# LinuxBoard_v1_0.net
KiCad netlist of a schematic drawn in EAGLE
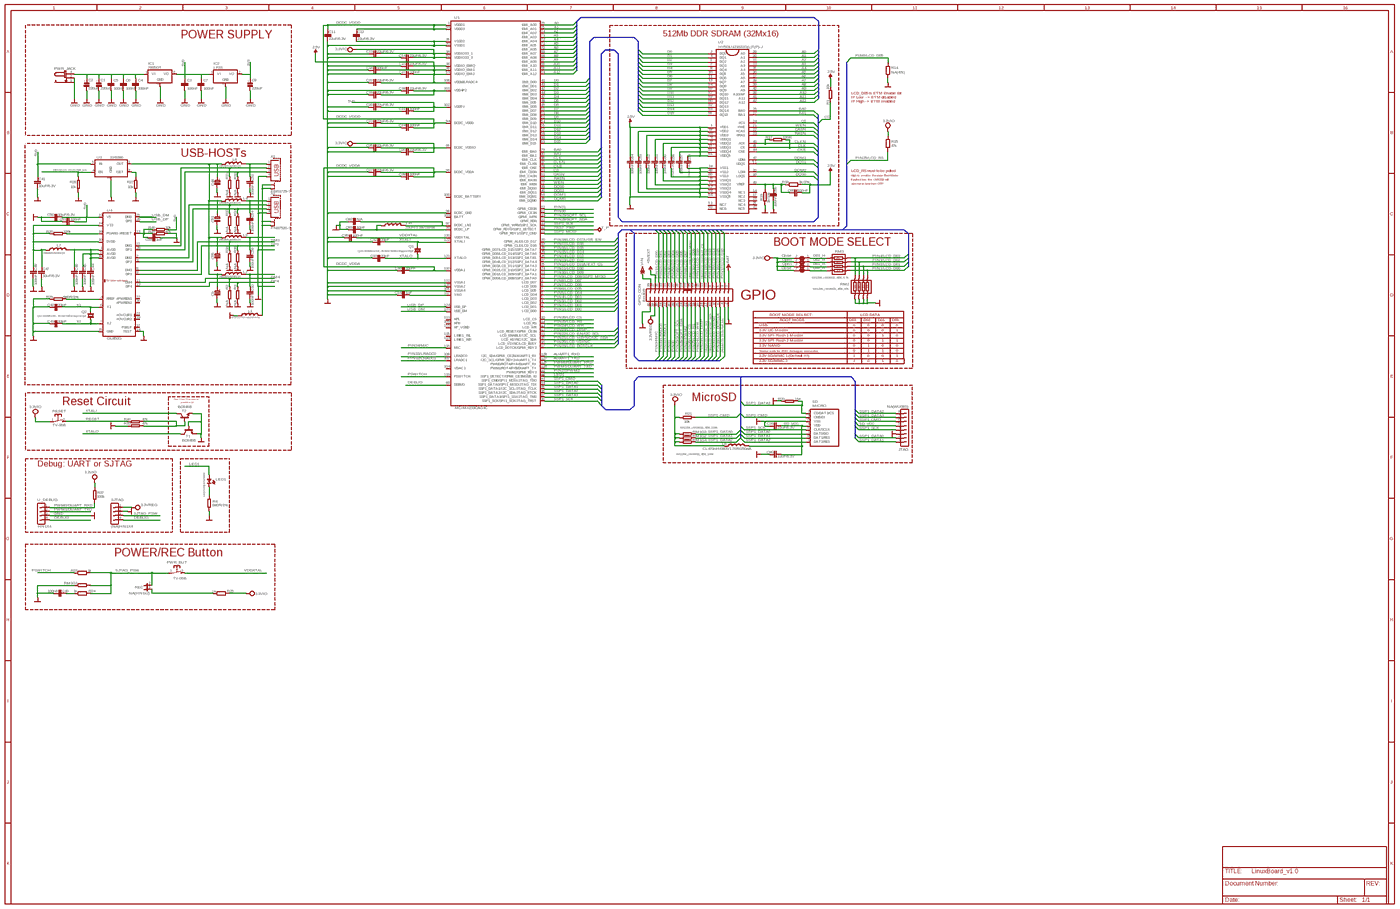
[diagram p0: schematic, sheet 1, overview]
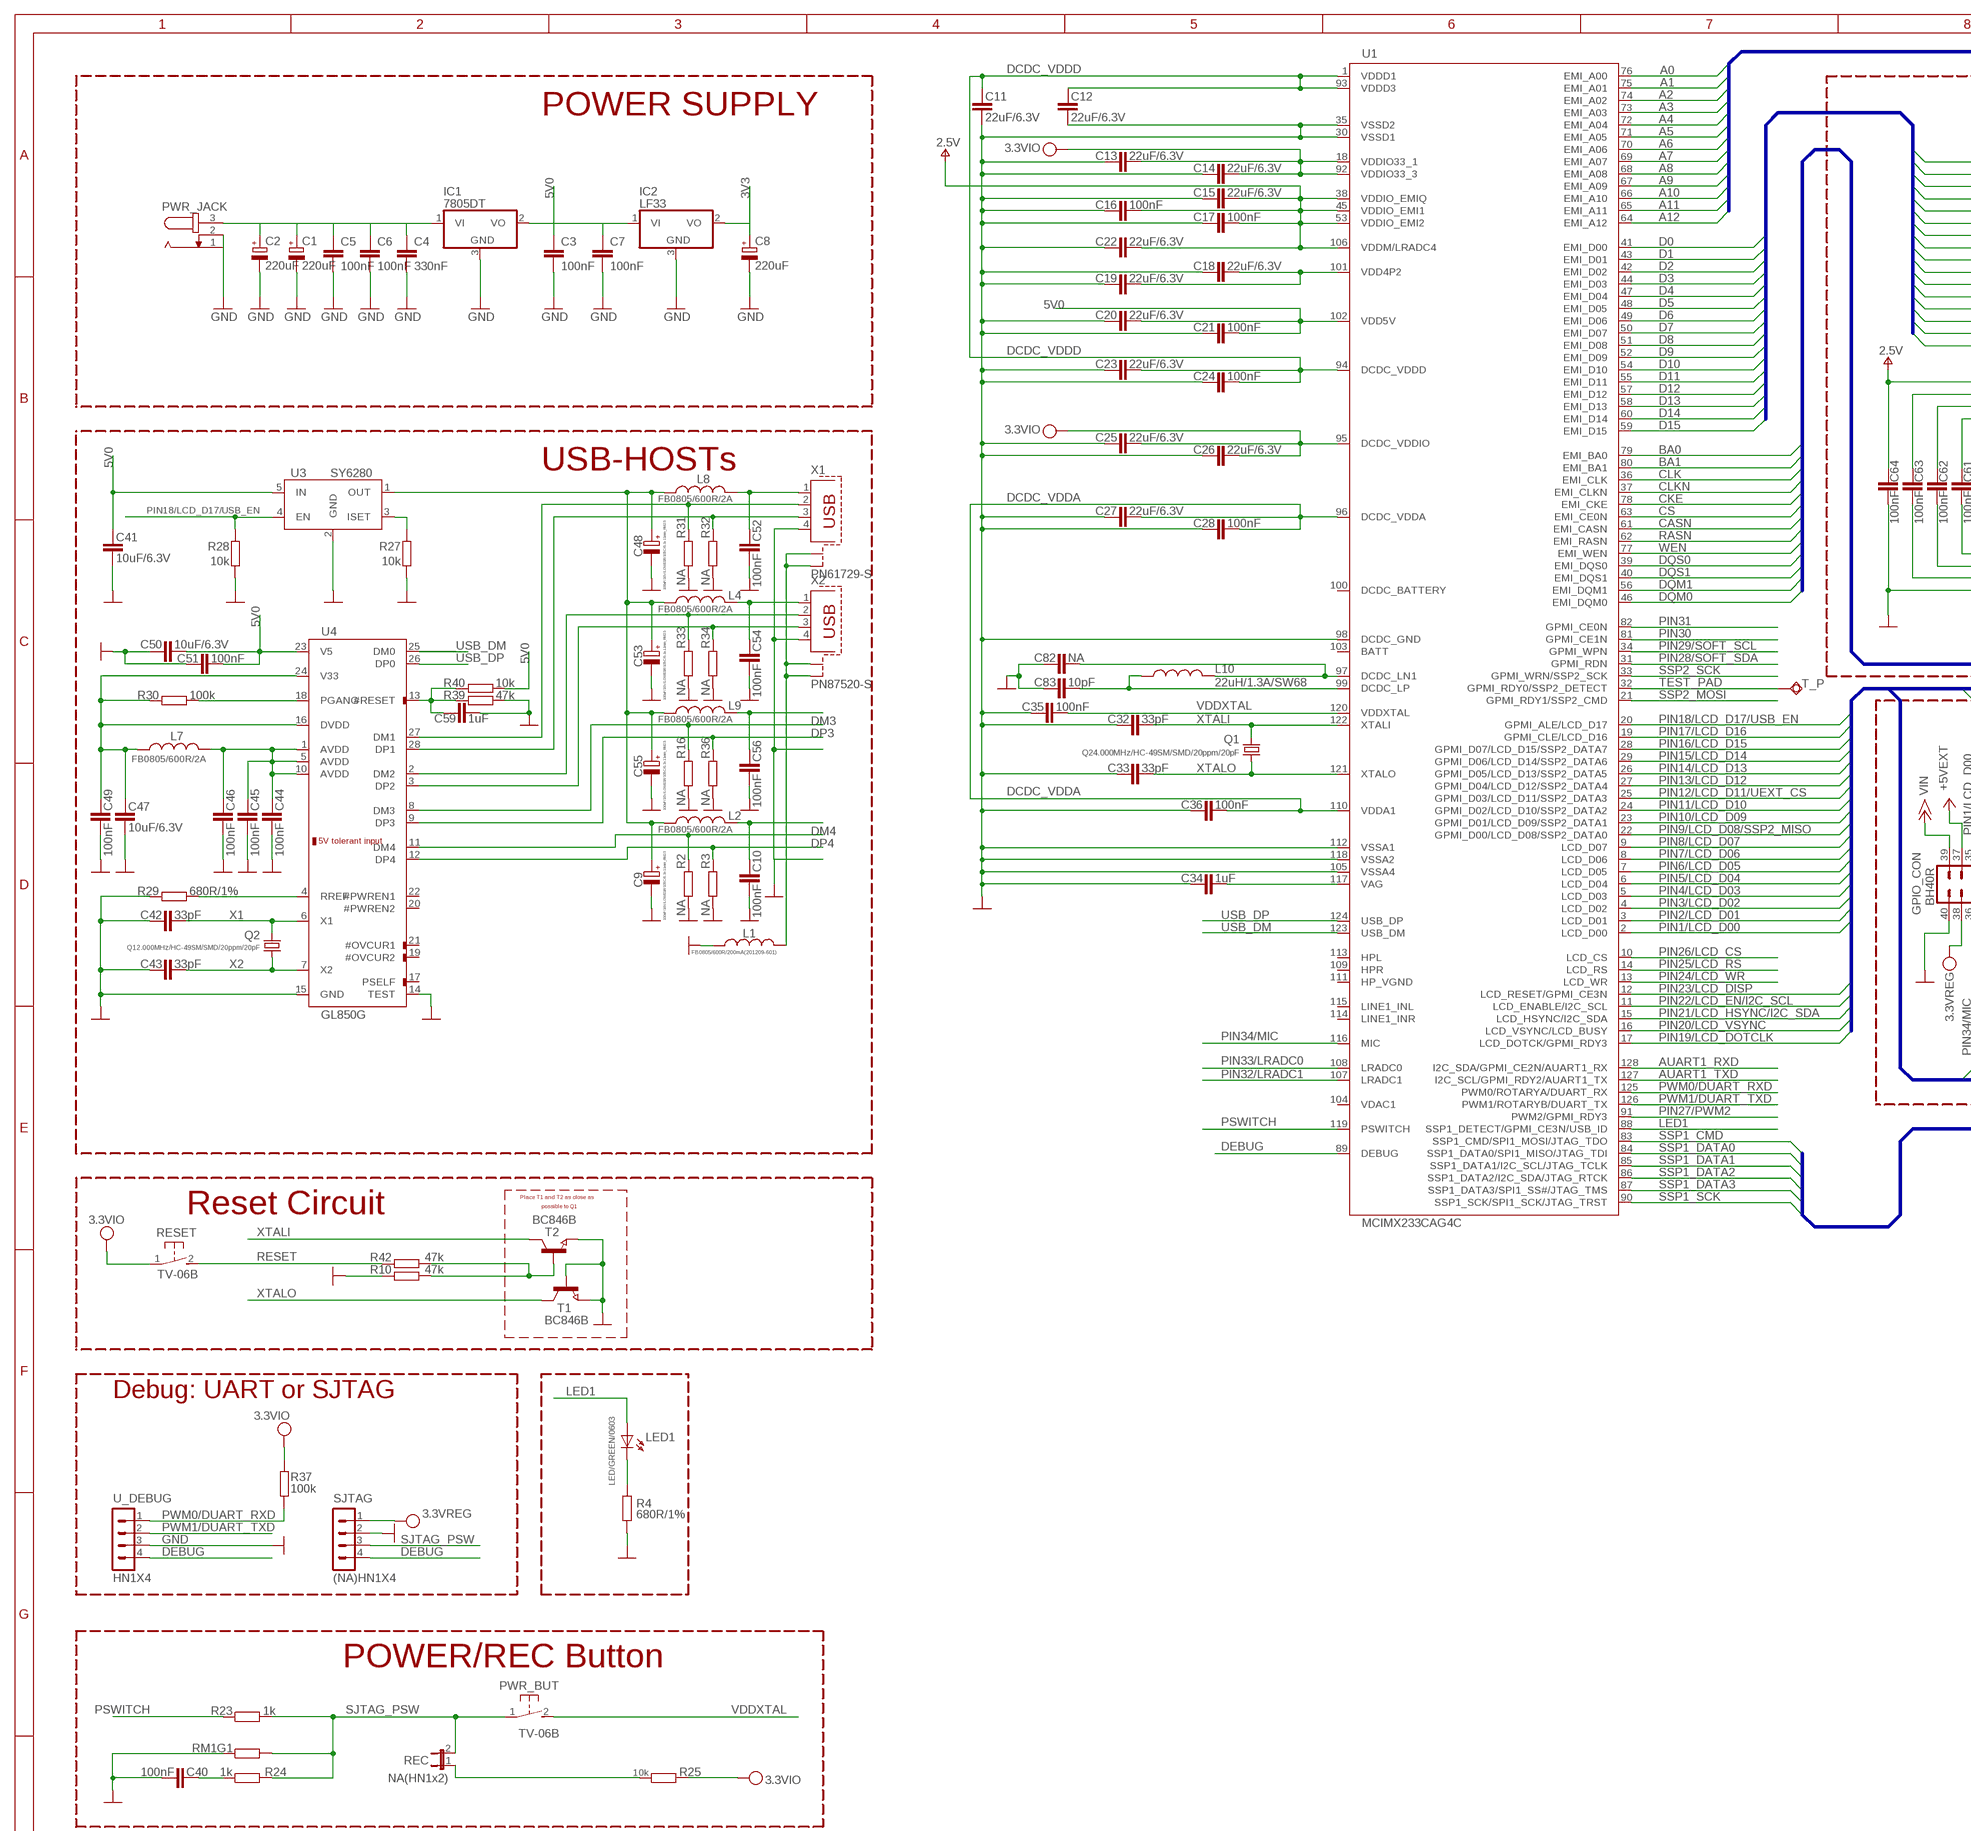
[diagram p1: schematic, sheet 1, part 1 of 4]
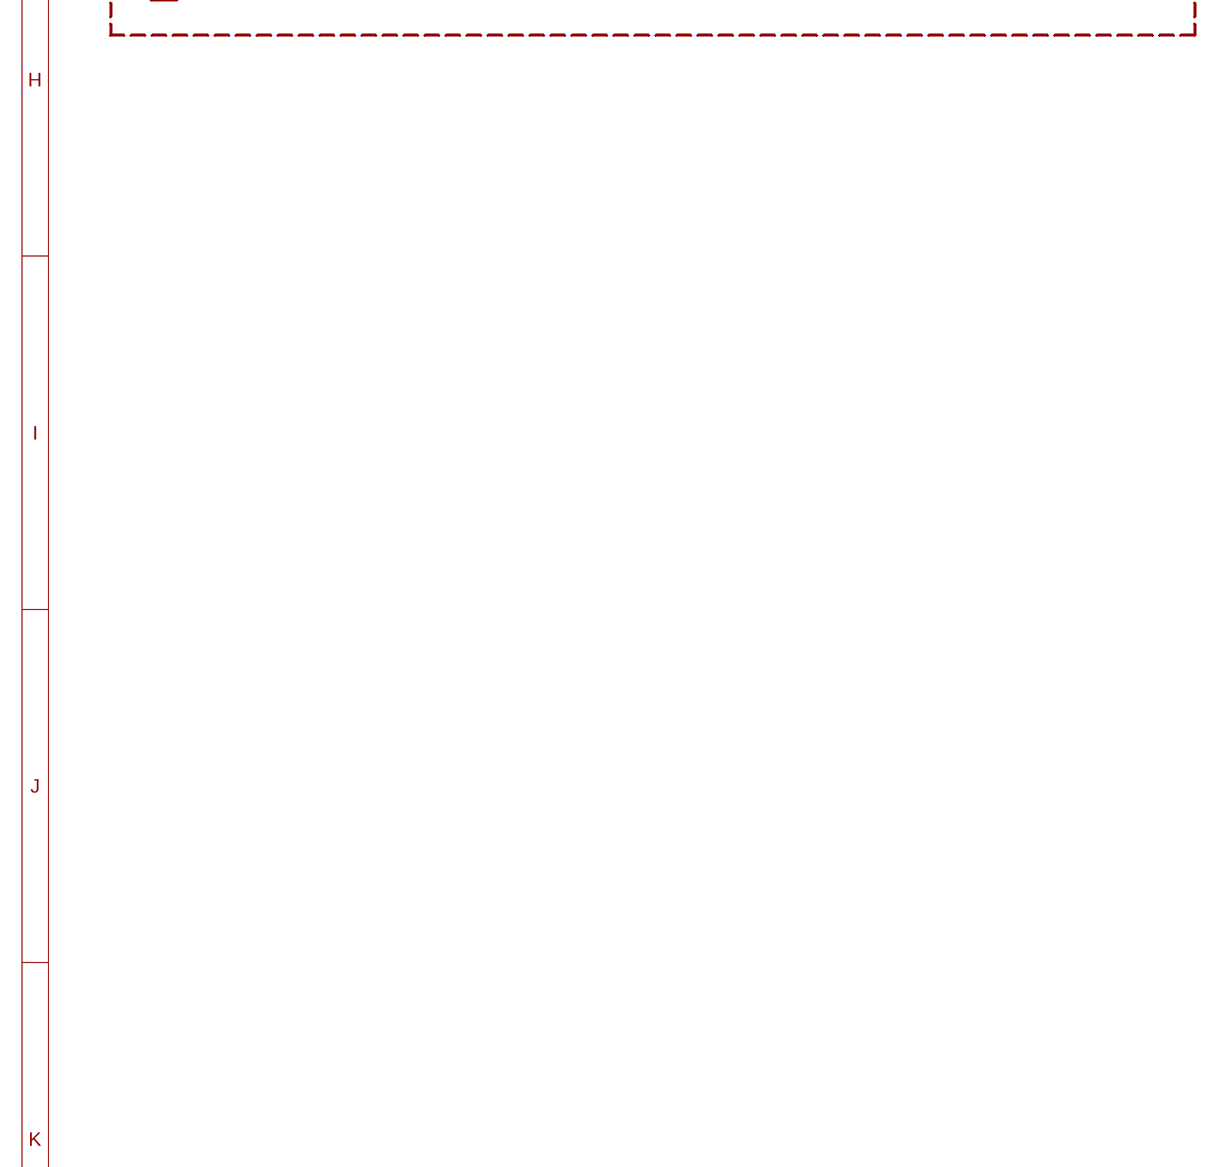
[diagram p2: schematic, sheet 1, part 2 of 4]
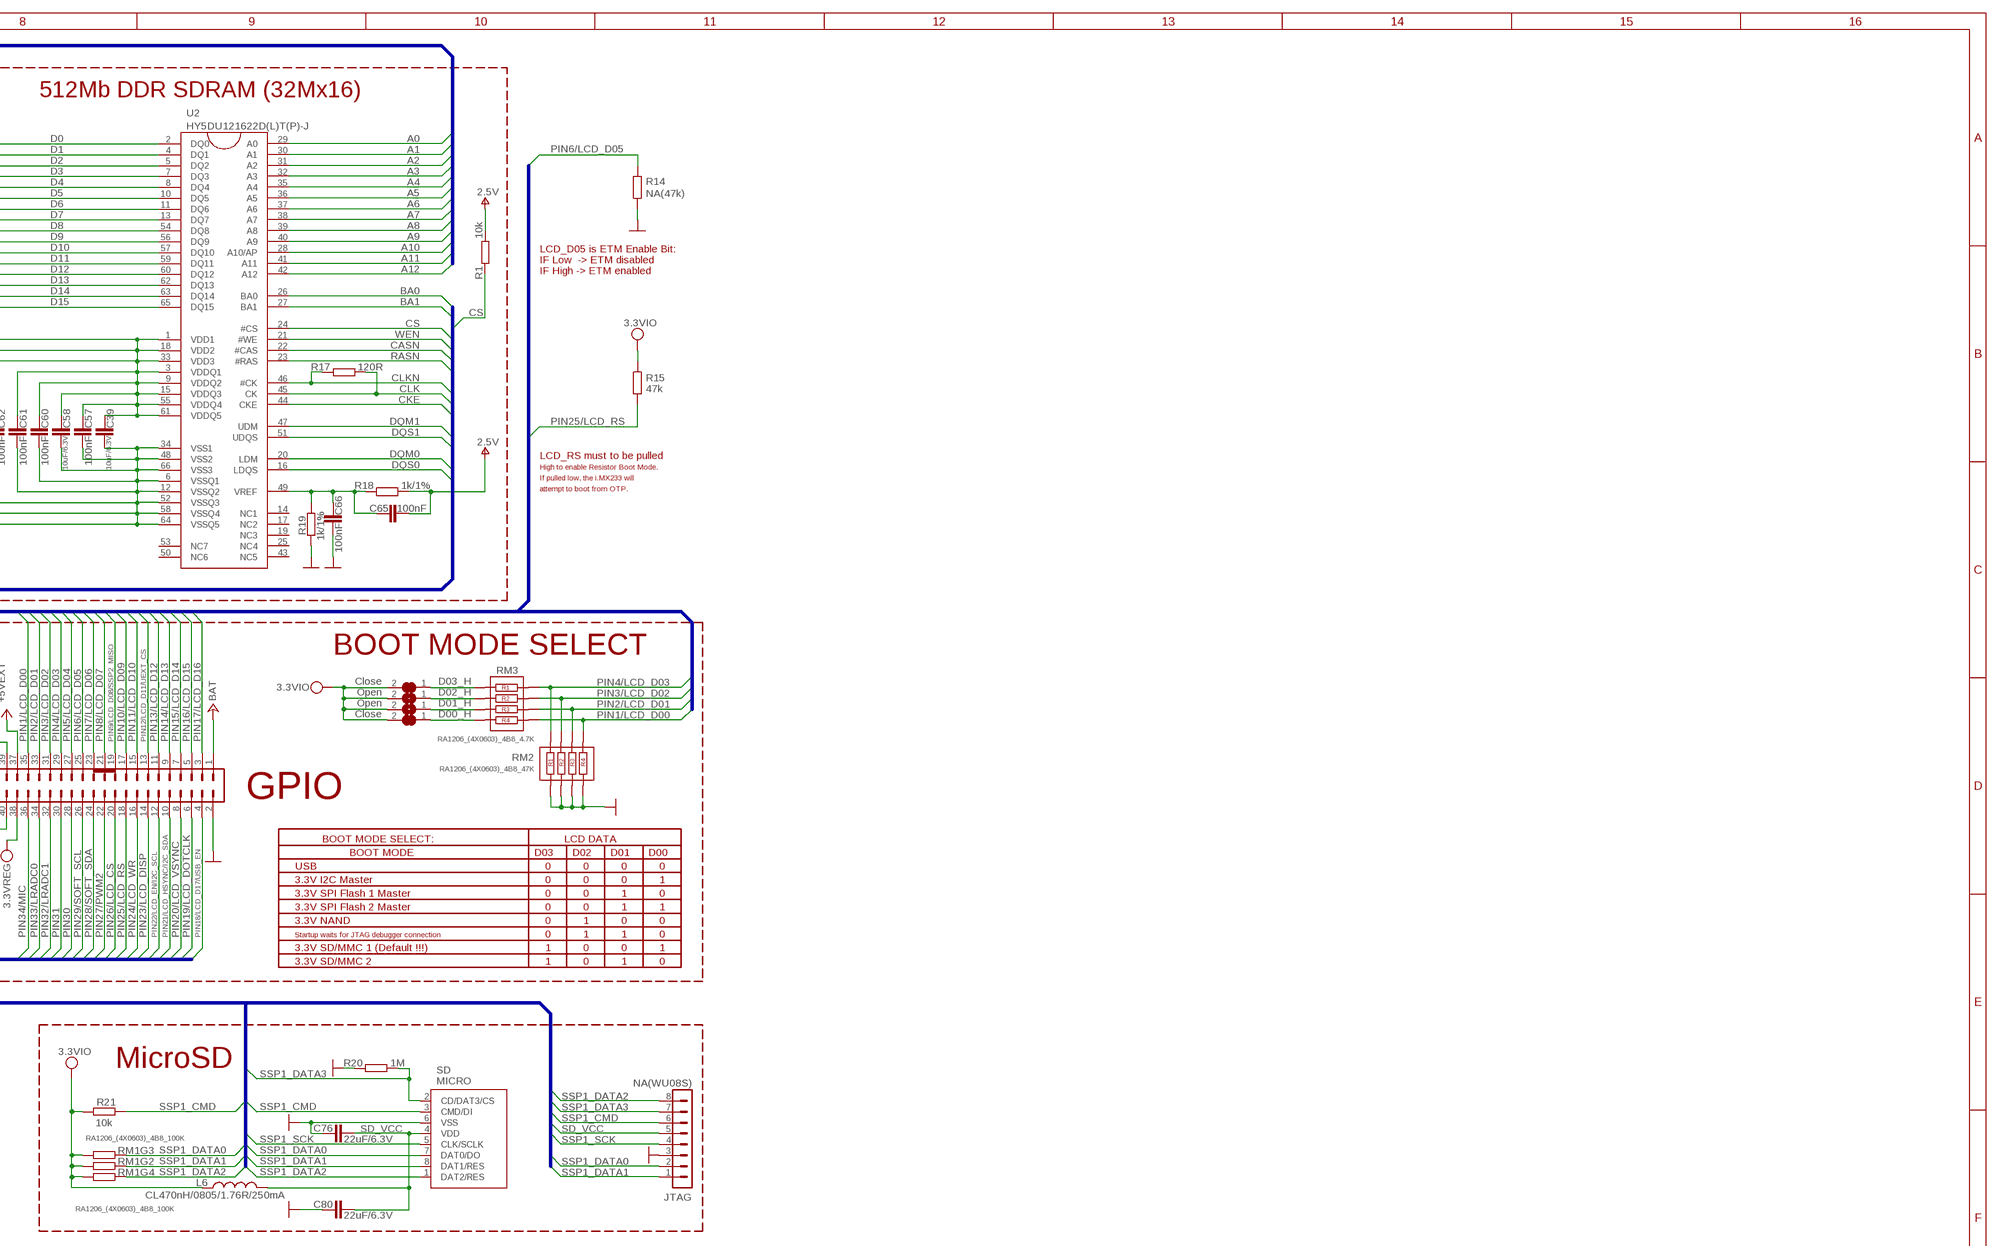
[diagram p3: schematic, sheet 1, part 3 of 4]
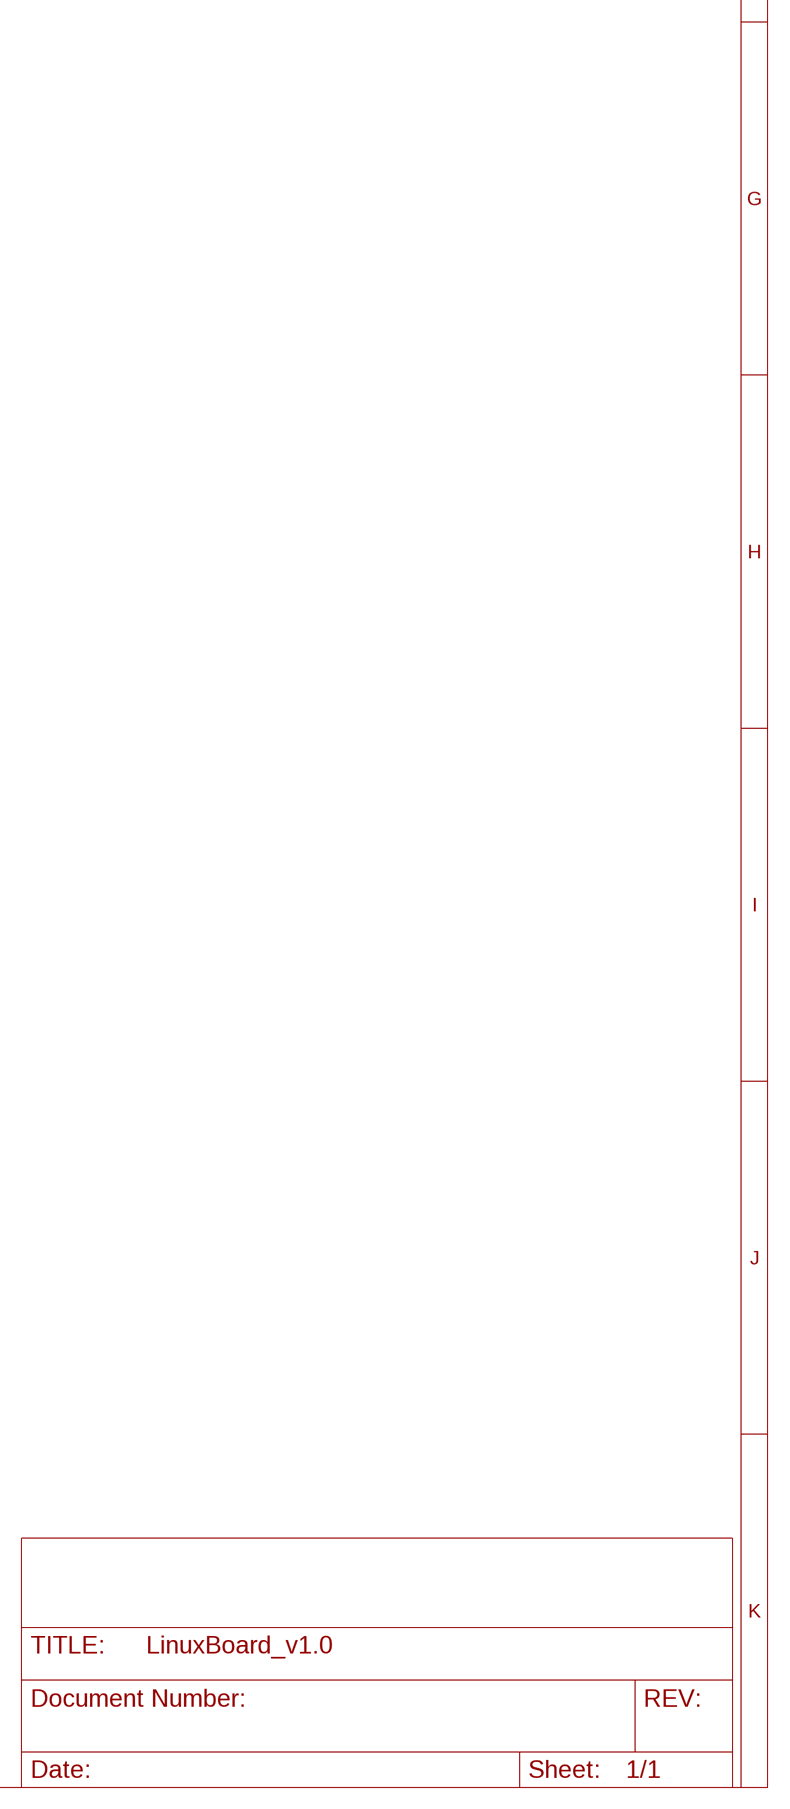
[diagram p4: schematic, sheet 1, part 4 of 4]

(export (version "E")
  (design (tool "Eeschema 10.0.6"))
  (components
    (comp (ref "C1")
      (value "220uF")
      (footprint "eagle-import:E2-5")
      (libsource (lib "eagle-import") (part "CPOL-EUE2-5"))
    )
    (comp (ref "C2")
      (value "220uF")
      (footprint "eagle-import:E2-5")
      (libsource (lib "eagle-import") (part "CPOL-EUE2-5"))
    )
    (comp (ref "C3")
      (value "100nF")
      (footprint "eagle-import:C0805")
      (libsource (lib "eagle-import") (part "C-EUC0805"))
    )
    (comp (ref "C4")
      (value "330nF")
      (footprint "eagle-import:C0805")
      (libsource (lib "eagle-import") (part "C-EUC0805"))
    )
    (comp (ref "C5")
      (value "100nF")
      (footprint "eagle-import:C0805")
      (libsource (lib "eagle-import") (part "C-EUC0805"))
    )
    (comp (ref "C6")
      (value "100nF")
      (footprint "eagle-import:C0805")
      (libsource (lib "eagle-import") (part "C-EUC0805"))
    )
    (comp (ref "C7")
      (value "100nF")
      (footprint "eagle-import:C0805")
      (libsource (lib "eagle-import") (part "C-EUC0805"))
    )
    (comp (ref "C8")
      (value "220uF")
      (footprint "eagle-import:E2-5")
      (libsource (lib "eagle-import") (part "CPOL-EUE2-5"))
    )
    (comp (ref "C9")
      (value "100uF/16V/LOWESR/105C/6.3x11mm_RM2.5")
      (footprint "eagle-import:E2,5-6,3")
      (libsource (lib "eagle-import") (part "CPOL-EUE2.5-6.3"))
    )
    (comp (ref "C10")
      (value "100nF")
      (footprint "eagle-import:C0603_DWS")
      (libsource (lib "eagle-import") (part "C-EUC0603_DWS"))
    )
    (comp (ref "C11")
      (value "22uF/6.3V")
      (footprint "eagle-import:C0805_5MIL_DWS")
      (libsource (lib "eagle-import") (part "C-EUC0805_5MIL_DWS"))
    )
    (comp (ref "C12")
      (value "22uF/6.3V")
      (footprint "eagle-import:C0805_5MIL_DWS")
      (libsource (lib "eagle-import") (part "C-EUC0805_5MIL_DWS"))
    )
    (comp (ref "C13")
      (value "22uF/6.3V")
      (footprint "eagle-import:C0805_5MIL_DWS")
      (libsource (lib "eagle-import") (part "C-EUC0805_5MIL_DWS"))
    )
    (comp (ref "C14")
      (value "22uF/6.3V")
      (footprint "eagle-import:C0805_5MIL_DWS")
      (libsource (lib "eagle-import") (part "C-EUC0805_5MIL_DWS"))
    )
    (comp (ref "C15")
      (value "22uF/6.3V")
      (footprint "eagle-import:C0805_5MIL_DWS")
      (libsource (lib "eagle-import") (part "C-EUC0805_5MIL_DWS"))
    )
    (comp (ref "C16")
      (value "100nF")
      (footprint "eagle-import:C0603_DWS")
      (libsource (lib "eagle-import") (part "C-EUC0603_DWS"))
    )
    (comp (ref "C17")
      (value "100nF")
      (footprint "eagle-import:C0603_DWS")
      (libsource (lib "eagle-import") (part "C-EUC0603_DWS"))
    )
    (comp (ref "C18")
      (value "22uF/6.3V")
      (footprint "eagle-import:C0805_5MIL_DWS")
      (libsource (lib "eagle-import") (part "C-EUC0805_5MIL_DWS"))
    )
    (comp (ref "C19")
      (value "22uF/6.3V")
      (footprint "eagle-import:C0805_5MIL_DWS")
      (libsource (lib "eagle-import") (part "C-EUC0805_5MIL_DWS"))
    )
    (comp (ref "C20")
      (value "22uF/6.3V")
      (footprint "eagle-import:C0805_5MIL_DWS")
      (libsource (lib "eagle-import") (part "C-EUC0805_5MIL_DWS"))
    )
    (comp (ref "C21")
      (value "100nF")
      (footprint "eagle-import:C0603_DWS")
      (libsource (lib "eagle-import") (part "C-EUC0603_DWS"))
    )
    (comp (ref "C22")
      (value "22uF/6.3V")
      (footprint "eagle-import:C0805_5MIL_DWS")
      (libsource (lib "eagle-import") (part "C-EUC0805_5MIL_DWS"))
    )
    (comp (ref "C23")
      (value "22uF/6.3V")
      (footprint "eagle-import:C0805_5MIL_DWS")
      (libsource (lib "eagle-import") (part "C-EUC0805_5MIL_DWS"))
    )
    (comp (ref "C24")
      (value "100nF")
      (footprint "eagle-import:C0603_DWS")
      (libsource (lib "eagle-import") (part "C-EUC0603_DWS"))
    )
    (comp (ref "C25")
      (value "22uF/6.3V")
      (footprint "eagle-import:C0805_5MIL_DWS")
      (libsource (lib "eagle-import") (part "C-EUC0805_5MIL_DWS"))
    )
    (comp (ref "C26")
      (value "22uF/6.3V")
      (footprint "eagle-import:C0805_5MIL_DWS")
      (libsource (lib "eagle-import") (part "C-EUC0805_5MIL_DWS"))
    )
    (comp (ref "C27")
      (value "22uF/6.3V")
      (footprint "eagle-import:C0805_5MIL_DWS")
      (libsource (lib "eagle-import") (part "C-EUC0805_5MIL_DWS"))
    )
    (comp (ref "C28")
      (value "100nF")
      (footprint "eagle-import:C0603_DWS")
      (libsource (lib "eagle-import") (part "C-EUC0603_DWS"))
    )
    (comp (ref "C32")
      (value "33pF")
      (footprint "eagle-import:C0603_DWS")
      (libsource (lib "eagle-import") (part "C-EUC0603_DWS"))
    )
    (comp (ref "C33")
      (value "33pF")
      (footprint "eagle-import:C0603_DWS")
      (libsource (lib "eagle-import") (part "C-EUC0603_DWS"))
    )
    (comp (ref "C34")
      (value "1uF")
      (footprint "eagle-import:C0603_DWS")
      (libsource (lib "eagle-import") (part "C-EUC0603_DWS"))
    )
    (comp (ref "C35")
      (value "100nF")
      (footprint "eagle-import:C0603_DWS")
      (libsource (lib "eagle-import") (part "C-EUC0603_DWS"))
    )
    (comp (ref "C36")
      (value "100nF")
      (footprint "eagle-import:C0603_DWS")
      (libsource (lib "eagle-import") (part "C-EUC0603_DWS"))
    )
    (comp (ref "C39")
      (value "10uF/6.3V")
      (footprint "eagle-import:C0603_DWS")
      (libsource (lib "eagle-import") (part "C-EUC0603_DWS"))
    )
    (comp (ref "C40")
      (value "100nF")
      (footprint "eagle-import:C0603_DWS")
      (libsource (lib "eagle-import") (part "C-EUC0603_DWS"))
    )
    (comp (ref "C41")
      (value "10uF/6.3V")
      (footprint "eagle-import:C0603_DWS")
      (libsource (lib "eagle-import") (part "C-EUC0603_DWS"))
    )
    (comp (ref "C42")
      (value "33pF")
      (footprint "eagle-import:C0603_DWS")
      (libsource (lib "eagle-import") (part "C-EUC0603_DWS"))
    )
    (comp (ref "C43")
      (value "33pF")
      (footprint "eagle-import:C0603_DWS")
      (libsource (lib "eagle-import") (part "C-EUC0603_DWS"))
    )
    (comp (ref "C44")
      (value "100nF")
      (footprint "eagle-import:C0603_DWS")
      (libsource (lib "eagle-import") (part "C-EUC0603_DWS"))
    )
    (comp (ref "C45")
      (value "100nF")
      (footprint "eagle-import:C0603_DWS")
      (libsource (lib "eagle-import") (part "C-EUC0603_DWS"))
    )
    (comp (ref "C46")
      (value "100nF")
      (footprint "eagle-import:C0603_DWS")
      (libsource (lib "eagle-import") (part "C-EUC0603_DWS"))
    )
    (comp (ref "C47")
      (value "10uF/6.3V")
      (footprint "eagle-import:C0603_DWS")
      (libsource (lib "eagle-import") (part "C-EUC0603_DWS"))
    )
    (comp (ref "C48")
      (value "100uF/16V/LOWESR/105C/6.3x11mm_RM2.5")
      (footprint "eagle-import:E2,5-6,3")
      (libsource (lib "eagle-import") (part "CPOL-EUE2.5-6.3"))
    )
    (comp (ref "C49")
      (value "100nF")
      (footprint "eagle-import:C0603_DWS")
      (libsource (lib "eagle-import") (part "C-EUC0603_DWS"))
    )
    (comp (ref "C50")
      (value "10uF/6.3V")
      (footprint "eagle-import:C0603_DWS")
      (libsource (lib "eagle-import") (part "C-EUC0603_DWS"))
    )
    (comp (ref "C51")
      (value "100nF")
      (footprint "eagle-import:C0603_DWS")
      (libsource (lib "eagle-import") (part "C-EUC0603_DWS"))
    )
    (comp (ref "C52")
      (value "100nF")
      (footprint "eagle-import:C0603_DWS")
      (libsource (lib "eagle-import") (part "C-EUC0603_DWS"))
    )
    (comp (ref "C53")
      (value "100uF/16V/LOWESR/105C/6.3x11mm_RM2.5")
      (footprint "eagle-import:E2,5-6,3")
      (libsource (lib "eagle-import") (part "CPOL-EUE2.5-6.3"))
    )
    (comp (ref "C54")
      (value "100nF")
      (footprint "eagle-import:C0603_DWS")
      (libsource (lib "eagle-import") (part "C-EUC0603_DWS"))
    )
    (comp (ref "C55")
      (value "100uF/16V/LOWESR/105C/6.3x11mm_RM2.5")
      (footprint "eagle-import:E2,5-6,3")
      (libsource (lib "eagle-import") (part "CPOL-EUE2.5-6.3"))
    )
    (comp (ref "C56")
      (value "100nF")
      (footprint "eagle-import:C0603_DWS")
      (libsource (lib "eagle-import") (part "C-EUC0603_DWS"))
    )
    (comp (ref "C57")
      (value "100nF")
      (footprint "eagle-import:C0603_DWS")
      (libsource (lib "eagle-import") (part "C-EUC0603_DWS"))
    )
    (comp (ref "C58")
      (value "10uF/6.3V")
      (footprint "eagle-import:C0603_DWS")
      (libsource (lib "eagle-import") (part "C-EUC0603_DWS"))
    )
    (comp (ref "C59")
      (value "1uF")
      (footprint "eagle-import:C0603_DWS")
      (libsource (lib "eagle-import") (part "C-EUC0603_DWS"))
    )
    (comp (ref "C60")
      (value "100nF")
      (footprint "eagle-import:C0603_DWS")
      (libsource (lib "eagle-import") (part "C-EUC0603_DWS"))
    )
    (comp (ref "C61")
      (value "100nF")
      (footprint "eagle-import:C0603_DWS")
      (libsource (lib "eagle-import") (part "C-EUC0603_DWS"))
    )
    (comp (ref "C62")
      (value "100nF")
      (footprint "eagle-import:C0603_DWS")
      (libsource (lib "eagle-import") (part "C-EUC0603_DWS"))
    )
    (comp (ref "C63")
      (value "100nF")
      (footprint "eagle-import:C0603_DWS")
      (libsource (lib "eagle-import") (part "C-EUC0603_DWS"))
    )
    (comp (ref "C64")
      (value "100nF")
      (footprint "eagle-import:C0603_DWS")
      (libsource (lib "eagle-import") (part "C-EUC0603_DWS"))
    )
    (comp (ref "C65")
      (value "100nF")
      (footprint "eagle-import:C0603_DWS")
      (libsource (lib "eagle-import") (part "C-EUC0603_DWS"))
    )
    (comp (ref "C66")
      (value "100nF")
      (footprint "eagle-import:C0603_DWS")
      (libsource (lib "eagle-import") (part "C-EUC0603_DWS"))
    )
    (comp (ref "C76")
      (value "22uF/6.3V")
      (footprint "eagle-import:C0805_5MIL_DWS")
      (libsource (lib "eagle-import") (part "C-EUC0805_5MIL_DWS"))
    )
    (comp (ref "C80")
      (value "22uF/6.3V")
      (footprint "eagle-import:C0805_5MIL_DWS")
      (libsource (lib "eagle-import") (part "C-EUC0805_5MIL_DWS"))
    )
    (comp (ref "C82")
      (value "NA")
      (footprint "eagle-import:C0603_DWS")
      (libsource (lib "eagle-import") (part "C-EUC0603_DWS"))
    )
    (comp (ref "C83")
      (value "10pF")
      (footprint "eagle-import:C0603_DWS")
      (libsource (lib "eagle-import") (part "C-EUC0603_DWS"))
    )
    (comp (ref "D00_H")
      (value "Close")
      (footprint "eagle-import:SJ_1_SMALLER")
      (libsource (lib "eagle-import") (part "SJSJ_SMALLER"))
    )
    (comp (ref "D01_H")
      (value "Open")
      (footprint "eagle-import:SJ_1_SMALLER")
      (libsource (lib "eagle-import") (part "SJSJ_SMALLER"))
    )
    (comp (ref "D02_H")
      (value "Open")
      (footprint "eagle-import:SJ_1_SMALLER")
      (libsource (lib "eagle-import") (part "SJSJ_SMALLER"))
    )
    (comp (ref "D03_H")
      (value "Close")
      (footprint "eagle-import:SJ_1_SMALLER")
      (libsource (lib "eagle-import") (part "SJSJ_SMALLER"))
    )
    (comp (ref "GPIO_CON")
      (value "BH40R")
      (footprint "eagle-import:BH40R")
      (libsource (lib "eagle-import") (part "ML40R"))
    )
    (comp (ref "IC1")
      (value "7805DT")
      (footprint "eagle-import:TO252")
      (libsource (lib "eagle-import") (part "78DT05"))
    )
    (comp (ref "IC2")
      (value "LF33")
      (footprint "eagle-import:TO252")
      (libsource (lib "eagle-import") (part "78DT05"))
    )
    (comp (ref "JTAG")
      (value "NA(WU08S)")
      (footprint "eagle-import:WU08S")
      (libsource (lib "eagle-import") (part "CON8WU08S"))
    )
    (comp (ref "L1")
      (value "FB0805/600R/200mA(201209-601)")
      (footprint "eagle-import:L0805_5MIL_DWS")
      (libsource (lib "eagle-import") (part "L-USL0805_5MIL_DWS"))
    )
    (comp (ref "L2")
      (value "FB0805/600R/2A")
      (footprint "eagle-import:L0805_5MIL_DWS")
      (libsource (lib "eagle-import") (part "L-USL0805_5MIL_DWS"))
    )
    (comp (ref "L4")
      (value "FB0805/600R/2A")
      (footprint "eagle-import:L0805_5MIL_DWS")
      (libsource (lib "eagle-import") (part "L-USL0805_5MIL_DWS"))
    )
    (comp (ref "L6")
      (value "CL470nH/0805/1.76R/250mA")
      (footprint "eagle-import:L0805_5MIL_DWS")
      (libsource (lib "eagle-import") (part "L-USL0805_5MIL_DWS"))
    )
    (comp (ref "L7")
      (value "FB0805/600R/2A")
      (footprint "eagle-import:L0805_5MIL_DWS")
      (libsource (lib "eagle-import") (part "L-USL0805_5MIL_DWS"))
    )
    (comp (ref "L8")
      (value "FB0805/600R/2A")
      (footprint "eagle-import:L0805_5MIL_DWS")
      (libsource (lib "eagle-import") (part "L-USL0805_5MIL_DWS"))
    )
    (comp (ref "L9")
      (value "FB0805/600R/2A")
      (footprint "eagle-import:L0805_5MIL_DWS")
      (libsource (lib "eagle-import") (part "L-USL0805_5MIL_DWS"))
    )
    (comp (ref "L10")
      (value "22uH/1.3A/SW68")
      (footprint "eagle-import:CD53")
      (libsource (lib "eagle-import") (part "L-USL_CD53"))
    )
    (comp (ref "LED1")
      (value "LED/GREEN/0603")
      (footprint "eagle-import:LED-0603")
      (libsource (lib "eagle-import") (part "LED0603DWS"))
    )
    (comp (ref "PWR_BUT")
      (value "TV-06B")
      (footprint "eagle-import:B3F-31XX")
      (libsource (lib "eagle-import") (part "31-XX"))
    )
    (comp (ref "PWR_JACK")
      (value "JACK-PLUG0")
      (footprint "eagle-import:SPC4077")
      (libsource (lib "eagle-import") (part "JACK-PLUG0"))
    )
    (comp (ref "Q1")
      (value "Q24.000MHz/HC-49SM/SMD/20ppm/20pF")
      (footprint "eagle-import:HC49_SMD2_THIN")
      (libsource (lib "eagle-import") (part "HC49/S1"))
    )
    (comp (ref "Q2")
      (value "Q12.000MHz/HC-49SM/SMD/20ppm/20pF")
      (footprint "eagle-import:HC49_SMD2_THIN")
      (libsource (lib "eagle-import") (part "HC49/S1"))
    )
    (comp (ref "R1")
      (value "10k")
      (footprint "eagle-import:R0603_5MIL_DWS")
      (libsource (lib "eagle-import") (part "R-EU_R0603_5MIL_DWS"))
    )
    (comp (ref "R2")
      (value "NA")
      (footprint "eagle-import:R0603_5MIL_DWS")
      (libsource (lib "eagle-import") (part "R-EU_R0603_5MIL_DWS"))
    )
    (comp (ref "R3")
      (value "NA")
      (footprint "eagle-import:R0603_5MIL_DWS")
      (libsource (lib "eagle-import") (part "R-EU_R0603_5MIL_DWS"))
    )
    (comp (ref "R4")
      (value "680R/1%")
      (footprint "eagle-import:R0603_5MIL_DWS")
      (libsource (lib "eagle-import") (part "R-EU_R0603_5MIL_DWS"))
    )
    (comp (ref "R10")
      (value "47k")
      (footprint "eagle-import:R0603_5MIL_DWS")
      (libsource (lib "eagle-import") (part "R-EU_R0603_5MIL_DWS"))
    )
    (comp (ref "R14")
      (value "NA(47k)")
      (footprint "eagle-import:R0603_5MIL_DWS")
      (libsource (lib "eagle-import") (part "R-EU_R0603_5MIL_DWS"))
    )
    (comp (ref "R15")
      (value "47k")
      (footprint "eagle-import:R0603_5MIL_DWS")
      (libsource (lib "eagle-import") (part "R-EU_R0603_5MIL_DWS"))
    )
    (comp (ref "R16")
      (value "NA")
      (footprint "eagle-import:R0603_5MIL_DWS")
      (libsource (lib "eagle-import") (part "R-EU_R0603_5MIL_DWS"))
    )
    (comp (ref "R17")
      (value "120R")
      (footprint "eagle-import:R0603_5MIL_DWS")
      (libsource (lib "eagle-import") (part "R-EU_R0603_5MIL_DWS"))
    )
    (comp (ref "R18")
      (value "1k/1%")
      (footprint "eagle-import:R0603_5MIL_DWS")
      (libsource (lib "eagle-import") (part "R-EU_R0603_5MIL_DWS"))
    )
    (comp (ref "R19")
      (value "1k/1%")
      (footprint "eagle-import:R0603_5MIL_DWS")
      (libsource (lib "eagle-import") (part "R-EU_R0603_5MIL_DWS"))
    )
    (comp (ref "R20")
      (value "1M")
      (footprint "eagle-import:R0603_5MIL_DWS")
      (libsource (lib "eagle-import") (part "R-EU_R0603_5MIL_DWS"))
    )
    (comp (ref "R21")
      (value "10k")
      (footprint "eagle-import:R0603_5MIL_DWS")
      (libsource (lib "eagle-import") (part "R-EU_R0603_5MIL_DWS"))
    )
    (comp (ref "R23")
      (value "1k")
      (footprint "eagle-import:R0603_5MIL_DWS")
      (libsource (lib "eagle-import") (part "R-EU_R0603_5MIL_DWS"))
    )
    (comp (ref "R24")
      (value "1k")
      (footprint "eagle-import:R0603_5MIL_DWS")
      (libsource (lib "eagle-import") (part "R-EU_R0603_5MIL_DWS"))
    )
    (comp (ref "R25")
      (value "10k")
      (footprint "eagle-import:R0603_5MIL_DWS_NA")
      (libsource (lib "eagle-import") (part "R-EU_R0603_5MIL_DWS_NA"))
    )
    (comp (ref "R27")
      (value "10k")
      (footprint "eagle-import:R0603_5MIL_DWS")
      (libsource (lib "eagle-import") (part "R-EU_R0603_5MIL_DWS"))
    )
    (comp (ref "R28")
      (value "10k")
      (footprint "eagle-import:R0603_5MIL_DWS")
      (libsource (lib "eagle-import") (part "R-EU_R0603_5MIL_DWS"))
    )
    (comp (ref "R29")
      (value "680R/1%")
      (footprint "eagle-import:R0603_5MIL_DWS")
      (libsource (lib "eagle-import") (part "R-EU_R0603_5MIL_DWS"))
    )
    (comp (ref "R30")
      (value "100k")
      (footprint "eagle-import:R0603_5MIL_DWS")
      (libsource (lib "eagle-import") (part "R-EU_R0603_5MIL_DWS"))
    )
    (comp (ref "R31")
      (value "NA")
      (footprint "eagle-import:R0603_5MIL_DWS")
      (libsource (lib "eagle-import") (part "R-EU_R0603_5MIL_DWS"))
    )
    (comp (ref "R32")
      (value "NA")
      (footprint "eagle-import:R0603_5MIL_DWS")
      (libsource (lib "eagle-import") (part "R-EU_R0603_5MIL_DWS"))
    )
    (comp (ref "R33")
      (value "NA")
      (footprint "eagle-import:R0603_5MIL_DWS")
      (libsource (lib "eagle-import") (part "R-EU_R0603_5MIL_DWS"))
    )
    (comp (ref "R34")
      (value "NA")
      (footprint "eagle-import:R0603_5MIL_DWS")
      (libsource (lib "eagle-import") (part "R-EU_R0603_5MIL_DWS"))
    )
    (comp (ref "R36")
      (value "NA")
      (footprint "eagle-import:R0603_5MIL_DWS")
      (libsource (lib "eagle-import") (part "R-EU_R0603_5MIL_DWS"))
    )
    (comp (ref "R37")
      (value "100k")
      (footprint "eagle-import:R0603_5MIL_DWS")
      (libsource (lib "eagle-import") (part "R-EU_R0603_5MIL_DWS"))
    )
    (comp (ref "R39")
      (value "47k")
      (footprint "eagle-import:R0603_5MIL_DWS")
      (libsource (lib "eagle-import") (part "R-EU_R0603_5MIL_DWS"))
    )
    (comp (ref "R40")
      (value "10k")
      (footprint "eagle-import:R0603_5MIL_DWS")
      (libsource (lib "eagle-import") (part "R-EU_R0603_5MIL_DWS"))
    )
    (comp (ref "R42")
      (value "47k")
      (footprint "eagle-import:R0603_5MIL_DWS")
      (libsource (lib "eagle-import") (part "R-EU_R0603_5MIL_DWS"))
    )
    (comp (ref "REC")
      (value "NA(HN1x2)")
      (footprint "eagle-import:JP1")
      (libsource (lib "eagle-import") (part "JP1E"))
    )
    (comp (ref "RESET")
      (value "TV-06B")
      (footprint "eagle-import:B3F-31XX")
      (libsource (lib "eagle-import") (part "31-XX"))
    )
    (comp (ref "RM1")
      (value "RA1206_(4X0603)_4B8_100K")
      (footprint "eagle-import:R_MATRIX_4")
      (libsource (lib "eagle-import") (part "R_MATRIX_4E"))
    )
    (comp (ref "RM2")
      (value "RA1206_(4X0603)_4B8_47K")
      (footprint "eagle-import:R_MATRIX_4")
      (libsource (lib "eagle-import") (part "R_MATRIX_4"))
    )
    (comp (ref "RM3")
      (value "RA1206_(4X0603)_4B8_4.7K")
      (footprint "eagle-import:R_MATRIX_4")
      (libsource (lib "eagle-import") (part "R_MATRIX_4"))
    )
    (comp (ref "SD")
      (value "MICRO")
      (footprint "eagle-import:TFR-MEM-CON")
      (libsource (lib "eagle-import") (part "MICRO_SD/MMC"))
    )
    (comp (ref "SJTAG")
      (value "(NA)HN1X4")
      (footprint "eagle-import:HN1X4")
      (libsource (lib "eagle-import") (part "CON4HN1X4"))
    )
    (comp (ref "T1")
      (value "BC846B")
      (footprint "eagle-import:SOT23")
      (libsource (lib "eagle-import") (part "NPN-TRANSISTOR_SOT23"))
    )
    (comp (ref "T2")
      (value "BC846B")
      (footprint "eagle-import:SOT23")
      (libsource (lib "eagle-import") (part "NPN-TRANSISTOR_SOT23"))
    )
    (comp (ref "T_P")
      (value "TESTPAD50/40")
      (footprint "eagle-import:SMD50_40")
      (libsource (lib "eagle-import") (part "TESTPAD50/40"))
    )
    (comp (ref "U1")
      (value "MCIMX233CAG4C")
      (footprint "eagle-import:TQFP128LD")
      (libsource (lib "eagle-import") (part "MCIMX233DAG4B_LD"))
    )
    (comp (ref "U2")
      (value "HY5DU121622D(L)T(P)-J")
      (footprint "eagle-import:66TSOP-II")
      (libsource (lib "eagle-import") (part "HY5DU121622D(L)T(P)-J"))
    )
    (comp (ref "U3")
      (value "SY6280")
      (footprint "eagle-import:SOT23-5")
      (libsource (lib "eagle-import") (part "SY6280"))
    )
    (comp (ref "U4")
      (value "GL850G")
      (footprint "eagle-import:SSOP28")
      (libsource (lib "eagle-import") (part "GL850G"))
    )
    (comp (ref "U_DEBUG")
      (value "HN1X4")
      (footprint "eagle-import:HN1X4")
      (libsource (lib "eagle-import") (part "CON4HN1X4"))
    )
    (comp (ref "X1")
      (value "PN61729-S")
      (footprint "eagle-import:PN61729-S")
      (libsource (lib "eagle-import") (part "PN61729-S"))
    )
    (comp (ref "X2")
      (value "PN87520-S")
      (footprint "eagle-import:PN87520-S")
      (libsource (lib "eagle-import") (part "PN87520-S"))
    )
  )
  (nets
    (net (code "1") (name "+5VEXT") (class "Default")
      (node (ref "GPIO_CON") (pin "37") (pinfunction "37_37") (pintype "passive"))
    )
    (net (code "2") (name "/3V3") (class "Default")
      (node (ref "C8") (pin "+") (pinfunction "+_+") (pintype "passive"))
      (node (ref "IC2") (pin "2") (pinfunction "VO_2") (pintype "passive"))
    )
    (net (code "3") (name "/5V0") (class "Default")
      (node (ref "C20") (pin "2") (pinfunction "2_2") (pintype "passive"))
      (node (ref "C21") (pin "2") (pinfunction "2_2") (pintype "passive"))
      (node (ref "C3") (pin "1") (pinfunction "1_1") (pintype "passive"))
      (node (ref "C41") (pin "1") (pinfunction "1_1") (pintype "passive"))
      (node (ref "C50") (pin "1") (pinfunction "1_1") (pintype "passive"))
      (node (ref "C51") (pin "1") (pinfunction "1_1") (pintype "passive"))
      (node (ref "C7") (pin "1") (pinfunction "1_1") (pintype "passive"))
      (node (ref "IC1") (pin "2") (pinfunction "VO_2") (pintype "passive"))
      (node (ref "IC2") (pin "1") (pinfunction "VI_1") (pintype "input"))
      (node (ref "R40") (pin "2") (pinfunction "2_2") (pintype "passive"))
      (node (ref "U1") (pin "102") (pinfunction "VDD5V_102") (pintype "power_in"))
      (node (ref "U3") (pin "5") (pinfunction "IN_5") (pintype "power_in"))
      (node (ref "U4") (pin "23") (pinfunction "V5_23") (pintype "power_in"))
    )
    (net (code "4") (name "/A0") (class "Default")
      (node (ref "U1") (pin "76") (pinfunction "EMI_A00_76") (pintype "bidirectional"))
      (node (ref "U2") (pin "29") (pinfunction "A0_29") (pintype "input"))
    )
    (net (code "5") (name "/A1") (class "Default")
      (node (ref "U1") (pin "75") (pinfunction "EMI_A01_75") (pintype "bidirectional"))
      (node (ref "U2") (pin "30") (pinfunction "A1_30") (pintype "input"))
    )
    (net (code "6") (name "/A2") (class "Default")
      (node (ref "U1") (pin "74") (pinfunction "EMI_A02_74") (pintype "bidirectional"))
      (node (ref "U2") (pin "31") (pinfunction "A2_31") (pintype "input"))
    )
    (net (code "7") (name "/A3") (class "Default")
      (node (ref "U1") (pin "73") (pinfunction "EMI_A03_73") (pintype "bidirectional"))
      (node (ref "U2") (pin "32") (pinfunction "A3_32") (pintype "input"))
    )
    (net (code "8") (name "/A4") (class "Default")
      (node (ref "U1") (pin "72") (pinfunction "EMI_A04_72") (pintype "bidirectional"))
      (node (ref "U2") (pin "35") (pinfunction "A4_35") (pintype "input"))
    )
    (net (code "9") (name "/A5") (class "Default")
      (node (ref "U1") (pin "71") (pinfunction "EMI_A05_71") (pintype "bidirectional"))
      (node (ref "U2") (pin "36") (pinfunction "A5_36") (pintype "input"))
    )
    (net (code "10") (name "/A6") (class "Default")
      (node (ref "U1") (pin "70") (pinfunction "EMI_A06_70") (pintype "bidirectional"))
      (node (ref "U2") (pin "37") (pinfunction "A6_37") (pintype "input"))
    )
    (net (code "11") (name "/A7") (class "Default")
      (node (ref "U1") (pin "69") (pinfunction "EMI_A07_69") (pintype "bidirectional"))
      (node (ref "U2") (pin "38") (pinfunction "A7_38") (pintype "input"))
    )
    (net (code "12") (name "/A8") (class "Default")
      (node (ref "U1") (pin "68") (pinfunction "EMI_A08_68") (pintype "bidirectional"))
      (node (ref "U2") (pin "39") (pinfunction "A8_39") (pintype "input"))
    )
    (net (code "13") (name "/A9") (class "Default")
      (node (ref "U1") (pin "67") (pinfunction "EMI_A09_67") (pintype "bidirectional"))
      (node (ref "U2") (pin "40") (pinfunction "A9_40") (pintype "input"))
    )
    (net (code "14") (name "/A10") (class "Default")
      (node (ref "U1") (pin "66") (pinfunction "EMI_A10_66") (pintype "bidirectional"))
      (node (ref "U2") (pin "28") (pinfunction "A10/AP_28") (pintype "input"))
    )
    (net (code "15") (name "/A11") (class "Default")
      (node (ref "U1") (pin "65") (pinfunction "EMI_A11_65") (pintype "bidirectional"))
      (node (ref "U2") (pin "41") (pinfunction "A11_41") (pintype "input"))
    )
    (net (code "16") (name "/A12") (class "Default")
      (node (ref "U1") (pin "64") (pinfunction "EMI_A12_64") (pintype "bidirectional"))
      (node (ref "U2") (pin "42") (pinfunction "A12_42") (pintype "input"))
    )
    (net (code "17") (name "/AUART1_RXD") (class "Default")
      (node (ref "U1") (pin "128") (pinfunction "I2C_SDA/GPMI_CE2N/AUART1_RX_128") (pintype "bidirectional"))
    )
    (net (code "18") (name "/AUART1_TXD") (class "Default")
      (node (ref "U1") (pin "127") (pinfunction "I2C_SCL/GPMI_RDY2/AUART1_TX_127") (pintype "bidirectional"))
    )
    (net (code "19") (name "/BA0") (class "Default")
      (node (ref "U1") (pin "79") (pinfunction "EMI_BA0_79") (pintype "output"))
      (node (ref "U2") (pin "26") (pinfunction "BA0_26") (pintype "input"))
    )
    (net (code "20") (name "/BA1") (class "Default")
      (node (ref "U1") (pin "80") (pinfunction "EMI_BA1_80") (pintype "output"))
      (node (ref "U2") (pin "27") (pinfunction "BA1_27") (pintype "input"))
    )
    (net (code "21") (name "/CASN") (class "Default")
      (node (ref "U1") (pin "61") (pinfunction "EMI_CASN_61") (pintype "output"))
      (node (ref "U2") (pin "22") (pinfunction "#CAS_22") (pintype "input"))
    )
    (net (code "22") (name "/CKE") (class "Default")
      (node (ref "U1") (pin "78") (pinfunction "EMI_CKE_78") (pintype "output"))
      (node (ref "U2") (pin "44") (pinfunction "CKE_44") (pintype "input"))
    )
    (net (code "23") (name "/CLK") (class "Default")
      (node (ref "R17") (pin "2") (pinfunction "2_2") (pintype "passive"))
      (node (ref "U1") (pin "36") (pinfunction "EMI_CLK_36") (pintype "output"))
      (node (ref "U2") (pin "45") (pinfunction "CK_45") (pintype "input"))
    )
    (net (code "24") (name "/CLKN") (class "Default")
      (node (ref "R17") (pin "1") (pinfunction "1_1") (pintype "passive"))
      (node (ref "U1") (pin "37") (pinfunction "EMI_CLKN_37") (pintype "output"))
      (node (ref "U2") (pin "46") (pinfunction "#CK_46") (pintype "input"))
    )
    (net (code "25") (name "/CS") (class "Default")
      (node (ref "R1") (pin "1") (pinfunction "1_1") (pintype "passive"))
      (node (ref "U1") (pin "63") (pinfunction "EMI_CE0N_63") (pintype "output"))
      (node (ref "U2") (pin "24") (pinfunction "#CS_24") (pintype "input"))
    )
    (net (code "26") (name "/D0") (class "Default")
      (node (ref "U1") (pin "41") (pinfunction "EMI_D00_41") (pintype "bidirectional"))
      (node (ref "U2") (pin "2") (pinfunction "DQ0_2") (pintype "bidirectional"))
    )
    (net (code "27") (name "/D1") (class "Default")
      (node (ref "U1") (pin "43") (pinfunction "EMI_D01_43") (pintype "bidirectional"))
      (node (ref "U2") (pin "4") (pinfunction "DQ1_4") (pintype "bidirectional"))
    )
    (net (code "28") (name "/D2") (class "Default")
      (node (ref "U1") (pin "42") (pinfunction "EMI_D02_42") (pintype "bidirectional"))
      (node (ref "U2") (pin "5") (pinfunction "DQ2_5") (pintype "bidirectional"))
    )
    (net (code "29") (name "/D3") (class "Default")
      (node (ref "U1") (pin "44") (pinfunction "EMI_D03_44") (pintype "bidirectional"))
      (node (ref "U2") (pin "7") (pinfunction "DQ3_7") (pintype "bidirectional"))
    )
    (net (code "30") (name "/D4") (class "Default")
      (node (ref "U1") (pin "47") (pinfunction "EMI_D04_47") (pintype "bidirectional"))
      (node (ref "U2") (pin "8") (pinfunction "DQ4_8") (pintype "bidirectional"))
    )
    (net (code "31") (name "/D5") (class "Default")
      (node (ref "U1") (pin "48") (pinfunction "EMI_D05_48") (pintype "bidirectional"))
      (node (ref "U2") (pin "10") (pinfunction "DQ5_10") (pintype "bidirectional"))
    )
    (net (code "32") (name "/D6") (class "Default")
      (node (ref "U1") (pin "49") (pinfunction "EMI_D06_49") (pintype "bidirectional"))
      (node (ref "U2") (pin "11") (pinfunction "DQ6_11") (pintype "bidirectional"))
    )
    (net (code "33") (name "/D7") (class "Default")
      (node (ref "U1") (pin "50") (pinfunction "EMI_D07_50") (pintype "bidirectional"))
      (node (ref "U2") (pin "13") (pinfunction "DQ7_13") (pintype "bidirectional"))
    )
    (net (code "34") (name "/D8") (class "Default")
      (node (ref "U1") (pin "51") (pinfunction "EMI_D08_51") (pintype "bidirectional"))
      (node (ref "U2") (pin "54") (pinfunction "DQ8_54") (pintype "bidirectional"))
    )
    (net (code "35") (name "/D9") (class "Default")
      (node (ref "U1") (pin "52") (pinfunction "EMI_D09_52") (pintype "bidirectional"))
      (node (ref "U2") (pin "56") (pinfunction "DQ9_56") (pintype "bidirectional"))
    )
    (net (code "36") (name "/D10") (class "Default")
      (node (ref "U1") (pin "54") (pinfunction "EMI_D10_54") (pintype "bidirectional"))
      (node (ref "U2") (pin "57") (pinfunction "DQ10_57") (pintype "bidirectional"))
    )
    (net (code "37") (name "/D11") (class "Default")
      (node (ref "U1") (pin "55") (pinfunction "EMI_D11_55") (pintype "bidirectional"))
      (node (ref "U2") (pin "59") (pinfunction "DQ11_59") (pintype "bidirectional"))
    )
    (net (code "38") (name "/D12") (class "Default")
      (node (ref "U1") (pin "57") (pinfunction "EMI_D12_57") (pintype "bidirectional"))
      (node (ref "U2") (pin "60") (pinfunction "DQ12_60") (pintype "bidirectional"))
    )
    (net (code "39") (name "/D13") (class "Default")
      (node (ref "U1") (pin "58") (pinfunction "EMI_D13_58") (pintype "bidirectional"))
      (node (ref "U2") (pin "62") (pinfunction "DQ13_62") (pintype "bidirectional"))
    )
    (net (code "40") (name "/D14") (class "Default")
      (node (ref "U1") (pin "60") (pinfunction "EMI_D14_60") (pintype "bidirectional"))
      (node (ref "U2") (pin "63") (pinfunction "DQ14_63") (pintype "bidirectional"))
    )
    (net (code "41") (name "/D15") (class "Default")
      (node (ref "U1") (pin "59") (pinfunction "EMI_D15_59") (pintype "bidirectional"))
      (node (ref "U2") (pin "65") (pinfunction "DQ15_65") (pintype "bidirectional"))
    )
    (net (code "42") (name "/DCDC_BATTERY") (class "Default")
      (node (ref "U1") (pin "100") (pinfunction "DCDC_BATTERY_100") (pintype "power_in"))
    )
    (net (code "43") (name "/DCDC_VDDA") (class "Default")
      (node (ref "C27") (pin "2") (pinfunction "2_2") (pintype "passive"))
      (node (ref "C28") (pin "2") (pinfunction "2_2") (pintype "passive"))
      (node (ref "C36") (pin "2") (pinfunction "2_2") (pintype "passive"))
      (node (ref "U1") (pin "110") (pinfunction "VDDA1_110") (pintype "power_in"))
      (node (ref "U1") (pin "96") (pinfunction "DCDC_VDDA_96") (pintype "power_in"))
    )
    (net (code "44") (name "/DCDC_VDDD") (class "Default")
      (node (ref "C11") (pin "2") (pinfunction "2_2") (pintype "passive"))
      (node (ref "C12") (pin "2") (pinfunction "2_2") (pintype "passive"))
      (node (ref "C23") (pin "2") (pinfunction "2_2") (pintype "passive"))
      (node (ref "C24") (pin "2") (pinfunction "2_2") (pintype "passive"))
      (node (ref "U1") (pin "1") (pinfunction "VDDD1_1") (pintype "power_in"))
      (node (ref "U1") (pin "93") (pinfunction "VDDD3_93") (pintype "power_in"))
      (node (ref "U1") (pin "94") (pinfunction "DCDC_VDDD_94") (pintype "power_in"))
    )
    (net (code "45") (name "/DEBUG") (class "Default")
      (node (ref "SJTAG") (pin "4") (pinfunction "4_4") (pintype "passive"))
      (node (ref "U1") (pin "89") (pinfunction "DEBUG_89") (pintype "bidirectional"))
      (node (ref "U_DEBUG") (pin "4") (pinfunction "4_4") (pintype "passive"))
    )
    (net (code "46") (name "/DM3") (class "Default")
      (node (ref "R16") (pin "2") (pinfunction "2_2") (pintype "passive"))
      (node (ref "U4") (pin "8") (pinfunction "DM3_8") (pintype "bidirectional"))
    )
    (net (code "47") (name "/DM4") (class "Default")
      (node (ref "R2") (pin "2") (pinfunction "2_2") (pintype "passive"))
      (node (ref "U4") (pin "11") (pinfunction "DM4_11") (pintype "bidirectional"))
    )
    (net (code "48") (name "/DP3") (class "Default")
      (node (ref "R36") (pin "2") (pinfunction "2_2") (pintype "passive"))
      (node (ref "U4") (pin "9") (pinfunction "DP3_9") (pintype "bidirectional"))
    )
    (net (code "49") (name "/DP4") (class "Default")
      (node (ref "R3") (pin "2") (pinfunction "2_2") (pintype "passive"))
      (node (ref "U4") (pin "12") (pinfunction "DP4_12") (pintype "bidirectional"))
    )
    (net (code "50") (name "/DQM0") (class "Default")
      (node (ref "U1") (pin "46") (pinfunction "EMI_DQM0_46") (pintype "output"))
      (node (ref "U2") (pin "20") (pinfunction "LDM_20") (pintype "input"))
    )
    (net (code "51") (name "/DQM1") (class "Default")
      (node (ref "U1") (pin "56") (pinfunction "EMI_DQM1_56") (pintype "output"))
      (node (ref "U2") (pin "47") (pinfunction "UDM_47") (pintype "input"))
    )
    (net (code "52") (name "/DQS0") (class "Default")
      (node (ref "U1") (pin "39") (pinfunction "EMI_DQS0_39") (pintype "output"))
      (node (ref "U2") (pin "16") (pinfunction "LDQS_16") (pintype "bidirectional"))
    )
    (net (code "53") (name "/DQS1") (class "Default")
      (node (ref "U1") (pin "40") (pinfunction "EMI_DQS1_40") (pintype "output"))
      (node (ref "U2") (pin "51") (pinfunction "UDQS_51") (pintype "input"))
    )
    (net (code "54") (name "/HP_VGND") (class "Default")
      (node (ref "U1") (pin "111") (pinfunction "HP_VGND_111") (pintype "power_in"))
    )
    (net (code "55") (name "/LED1") (class "Default")
      (node (ref "LED1") (pin "A") (pinfunction "A_A") (pintype "passive"))
      (node (ref "U1") (pin "88") (pinfunction "SSP1_DETECT/GPMI_CE3N/USB_ID_88") (pintype "bidirectional"))
    )
    (net (code "56") (name "/PIN1{slash}LCD_D00") (class "Default")
      (node (ref "GPIO_CON") (pin "35") (pinfunction "35_35") (pintype "passive"))
      (node (ref "RM2") (pin "4.2") (pinfunction "4.2_4.2") (pintype "passive"))
      (node (ref "RM3") (pin "4.1") (pinfunction "4.1_4.1") (pintype "passive"))
      (node (ref "U1") (pin "2") (pinfunction "LCD_D00_2") (pintype "bidirectional"))
    )
    (net (code "57") (name "/PIN2{slash}LCD_D01") (class "Default")
      (node (ref "GPIO_CON") (pin "33") (pinfunction "33_33") (pintype "passive"))
      (node (ref "RM2") (pin "3.2") (pinfunction "3.2_3.2") (pintype "passive"))
      (node (ref "RM3") (pin "3.1") (pinfunction "3.1_3.1") (pintype "passive"))
      (node (ref "U1") (pin "3") (pinfunction "LCD_D01_3") (pintype "bidirectional"))
    )
    (net (code "58") (name "/PIN3{slash}LCD_D02") (class "Default")
      (node (ref "GPIO_CON") (pin "31") (pinfunction "31_31") (pintype "passive"))
      (node (ref "RM2") (pin "2.2") (pinfunction "2.2_2.2") (pintype "passive"))
      (node (ref "RM3") (pin "2.1") (pinfunction "2.1_2.1") (pintype "passive"))
      (node (ref "U1") (pin "4") (pinfunction "LCD_D02_4") (pintype "bidirectional"))
    )
    (net (code "59") (name "/PIN4{slash}LCD_D03") (class "Default")
      (node (ref "GPIO_CON") (pin "29") (pinfunction "29_29") (pintype "passive"))
      (node (ref "RM2") (pin "1.2") (pinfunction "1.2_1.2") (pintype "passive"))
      (node (ref "RM3") (pin "1.1") (pinfunction "1.1_1.1") (pintype "passive"))
      (node (ref "U1") (pin "5") (pinfunction "LCD_D03_5") (pintype "bidirectional"))
    )
    (net (code "60") (name "/PIN5{slash}LCD_D04") (class "Default")
      (node (ref "GPIO_CON") (pin "27") (pinfunction "27_27") (pintype "passive"))
      (node (ref "U1") (pin "6") (pinfunction "LCD_D04_6") (pintype "bidirectional"))
    )
    (net (code "61") (name "/PIN6{slash}LCD_D05") (class "Default")
      (node (ref "GPIO_CON") (pin "25") (pinfunction "25_25") (pintype "passive"))
      (node (ref "R14") (pin "2") (pinfunction "2_2") (pintype "passive"))
      (node (ref "U1") (pin "7") (pinfunction "LCD_D05_7") (pintype "bidirectional"))
    )
    (net (code "62") (name "/PIN7{slash}LCD_D06") (class "Default")
      (node (ref "GPIO_CON") (pin "23") (pinfunction "23_23") (pintype "passive"))
      (node (ref "U1") (pin "8") (pinfunction "LCD_D06_8") (pintype "bidirectional"))
    )
    (net (code "63") (name "/PIN8{slash}LCD_D07") (class "Default")
      (node (ref "GPIO_CON") (pin "21") (pinfunction "21_21") (pintype "passive"))
      (node (ref "U1") (pin "9") (pinfunction "LCD_D07_9") (pintype "bidirectional"))
    )
    (net (code "64") (name "/PIN9{slash}LCD_D08{slash}SSP2_MISO") (class "Default")
      (node (ref "GPIO_CON") (pin "19") (pinfunction "19_19") (pintype "passive"))
      (node (ref "U1") (pin "22") (pinfunction "GPMI_D00/LCD_D08/SSP2_DATA0_22") (pintype "bidirectional"))
    )
    (net (code "65") (name "/PIN10{slash}LCD_D09") (class "Default")
      (node (ref "GPIO_CON") (pin "17") (pinfunction "17_17") (pintype "passive"))
      (node (ref "U1") (pin "23") (pinfunction "GPMI_D01/LCD_D09/SSP2_DATA1_23") (pintype "bidirectional"))
    )
    (net (code "66") (name "/PIN11{slash}LCD_D10") (class "Default")
      (node (ref "GPIO_CON") (pin "15") (pinfunction "15_15") (pintype "passive"))
      (node (ref "U1") (pin "24") (pinfunction "GPMI_D02/LCD_D10/SSP2_DATA2_24") (pintype "bidirectional"))
    )
    (net (code "67") (name "/PIN12{slash}LCD_D11{slash}UEXT_CS") (class "Default")
      (node (ref "GPIO_CON") (pin "13") (pinfunction "13_13") (pintype "passive"))
      (node (ref "U1") (pin "25") (pinfunction "GPMI_D03/LCD_D11/SSP2_DATA3_25") (pintype "bidirectional"))
    )
    (net (code "68") (name "/PIN13{slash}LCD_D12") (class "Default")
      (node (ref "GPIO_CON") (pin "11") (pinfunction "11_11") (pintype "passive"))
      (node (ref "U1") (pin "27") (pinfunction "GPMI_D04/LCD_D12/SSP2_DATA4_27") (pintype "bidirectional"))
    )
    (net (code "69") (name "/PIN14{slash}LCD_D13") (class "Default")
      (node (ref "GPIO_CON") (pin "9") (pinfunction "9_9") (pintype "passive"))
      (node (ref "U1") (pin "26") (pinfunction "GPMI_D05/LCD_D13/SSP2_DATA5_26") (pintype "bidirectional"))
    )
    (net (code "70") (name "/PIN15{slash}LCD_D14") (class "Default")
      (node (ref "GPIO_CON") (pin "7") (pinfunction "7_7") (pintype "passive"))
      (node (ref "U1") (pin "29") (pinfunction "GPMI_D06/LCD_D14/SSP2_DATA6_29") (pintype "bidirectional"))
    )
    (net (code "71") (name "/PIN16{slash}LCD_D15") (class "Default")
      (node (ref "GPIO_CON") (pin "5") (pinfunction "5_5") (pintype "passive"))
      (node (ref "U1") (pin "28") (pinfunction "GPMI_D07/LCD_D15/SSP2_DATA7_28") (pintype "bidirectional"))
    )
    (net (code "72") (name "/PIN17{slash}LCD_D16") (class "Default")
      (node (ref "GPIO_CON") (pin "3") (pinfunction "3_3") (pintype "passive"))
      (node (ref "U1") (pin "19") (pinfunction "GPMI_CLE/LCD_D16_19") (pintype "bidirectional"))
    )
    (net (code "73") (name "/PIN18{slash}LCD_D17{slash}USB_EN") (class "Default")
      (node (ref "GPIO_CON") (pin "4") (pinfunction "4_4") (pintype "passive"))
      (node (ref "R28") (pin "2") (pinfunction "2_2") (pintype "passive"))
      (node (ref "U1") (pin "20") (pinfunction "GPMI_ALE/LCD_D17_20") (pintype "bidirectional"))
      (node (ref "U3") (pin "4") (pinfunction "EN_4") (pintype "bidirectional"))
    )
    (net (code "74") (name "/PIN19{slash}LCD_DOTCLK") (class "Default")
      (node (ref "GPIO_CON") (pin "6") (pinfunction "6_6") (pintype "passive"))
      (node (ref "U1") (pin "17") (pinfunction "LCD_DOTCK/GPMI_RDY3_17") (pintype "bidirectional"))
    )
    (net (code "75") (name "/PIN20{slash}LCD_VSYNC") (class "Default")
      (node (ref "GPIO_CON") (pin "8") (pinfunction "8_8") (pintype "passive"))
      (node (ref "U1") (pin "16") (pinfunction "LCD_VSYNC/LCD_BUSY_16") (pintype "bidirectional"))
    )
    (net (code "76") (name "/PIN21{slash}LCD_HSYNC{slash}I2C_SDA") (class "Default")
      (node (ref "GPIO_CON") (pin "10") (pinfunction "10_10") (pintype "passive"))
      (node (ref "U1") (pin "15") (pinfunction "LCD_HSYNC/I2C_SDA_15") (pintype "bidirectional"))
    )
    (net (code "77") (name "/PIN22{slash}LCD_EN{slash}I2C_SCL") (class "Default")
      (node (ref "GPIO_CON") (pin "12") (pinfunction "12_12") (pintype "passive"))
      (node (ref "U1") (pin "11") (pinfunction "LCD_ENABLE/I2C_SCL_11") (pintype "bidirectional"))
    )
    (net (code "78") (name "/PIN23{slash}LCD_DISP") (class "Default")
      (node (ref "GPIO_CON") (pin "14") (pinfunction "14_14") (pintype "passive"))
      (node (ref "U1") (pin "12") (pinfunction "LCD_RESET/GPMI_CE3N_12") (pintype "bidirectional"))
    )
    (net (code "79") (name "/PIN24{slash}LCD_WR") (class "Default")
      (node (ref "GPIO_CON") (pin "16") (pinfunction "16_16") (pintype "passive"))
      (node (ref "U1") (pin "13") (pinfunction "LCD_WR_13") (pintype "bidirectional"))
    )
    (net (code "80") (name "/PIN25{slash}LCD_RS") (class "Default")
      (node (ref "GPIO_CON") (pin "18") (pinfunction "18_18") (pintype "passive"))
      (node (ref "R15") (pin "2") (pinfunction "2_2") (pintype "passive"))
      (node (ref "U1") (pin "14") (pinfunction "LCD_RS_14") (pintype "bidirectional"))
    )
    (net (code "81") (name "/PIN26{slash}LCD_CS") (class "Default")
      (node (ref "GPIO_CON") (pin "20") (pinfunction "20_20") (pintype "passive"))
      (node (ref "U1") (pin "10") (pinfunction "LCD_CS_10") (pintype "bidirectional"))
    )
    (net (code "82") (name "/PIN27{slash}PWM2") (class "Default")
      (node (ref "GPIO_CON") (pin "22") (pinfunction "22_22") (pintype "passive"))
      (node (ref "U1") (pin "91") (pinfunction "PWM2/GPMI_RDY3_91") (pintype "bidirectional"))
    )
    (net (code "83") (name "/PIN28{slash}SOFT_SDA") (class "Default")
      (node (ref "GPIO_CON") (pin "24") (pinfunction "24_24") (pintype "passive"))
      (node (ref "U1") (pin "31") (pinfunction "GPMI_RDN_31") (pintype "bidirectional"))
    )
    (net (code "84") (name "/PIN29{slash}SOFT_SCL") (class "Default")
      (node (ref "GPIO_CON") (pin "26") (pinfunction "26_26") (pintype "passive"))
      (node (ref "U1") (pin "34") (pinfunction "GPMI_WPN_34") (pintype "bidirectional"))
    )
    (net (code "85") (name "/PIN30") (class "Default")
      (node (ref "GPIO_CON") (pin "28") (pinfunction "28_28") (pintype "passive"))
      (node (ref "U1") (pin "81") (pinfunction "GPMI_CE1N_81") (pintype "bidirectional"))
    )
    (net (code "86") (name "/PIN31") (class "Default")
      (node (ref "GPIO_CON") (pin "30") (pinfunction "30_30") (pintype "passive"))
      (node (ref "U1") (pin "82") (pinfunction "GPMI_CE0N_82") (pintype "bidirectional"))
    )
    (net (code "87") (name "/PIN32{slash}LRADC1") (class "Default")
      (node (ref "GPIO_CON") (pin "32") (pinfunction "32_32") (pintype "passive"))
      (node (ref "U1") (pin "107") (pinfunction "LRADC1_107") (pintype "bidirectional"))
    )
    (net (code "88") (name "/PIN33{slash}LRADC0") (class "Default")
      (node (ref "GPIO_CON") (pin "34") (pinfunction "34_34") (pintype "passive"))
      (node (ref "U1") (pin "108") (pinfunction "LRADC0_108") (pintype "bidirectional"))
    )
    (net (code "89") (name "/PIN34{slash}MIC") (class "Default")
      (node (ref "GPIO_CON") (pin "36") (pinfunction "36_36") (pintype "passive"))
      (node (ref "U1") (pin "116") (pinfunction "MIC_116") (pintype "input"))
    )
    (net (code "90") (name "/PSWITCH") (class "Default")
      (node (ref "R23") (pin "1") (pinfunction "1_1") (pintype "passive"))
      (node (ref "U1") (pin "119") (pinfunction "PSWITCH_119") (pintype "input"))
    )
    (net (code "91") (name "/PWM0{slash}DUART_RXD") (class "Default")
      (node (ref "R37") (pin "1") (pinfunction "1_1") (pintype "passive"))
      (node (ref "U1") (pin "125") (pinfunction "PWM0/ROTARYA/DUART_RX_125") (pintype "bidirectional"))
      (node (ref "U_DEBUG") (pin "1") (pinfunction "1_1") (pintype "passive"))
    )
    (net (code "92") (name "/PWM1{slash}DUART_TXD") (class "Default")
      (node (ref "U1") (pin "126") (pinfunction "PWM1/ROTARYB/DUART_TX_126") (pintype "bidirectional"))
      (node (ref "U_DEBUG") (pin "2") (pinfunction "2_2") (pintype "passive"))
    )
    (net (code "93") (name "/RASN") (class "Default")
      (node (ref "U1") (pin "62") (pinfunction "EMI_RASN_62") (pintype "output"))
      (node (ref "U2") (pin "23") (pinfunction "#RAS_23") (pintype "input"))
    )
    (net (code "94") (name "/RESET") (class "Default")
      (node (ref "R42") (pin "2") (pinfunction "2_2") (pintype "passive"))
      (node (ref "RESET") (pin "2") (pinfunction "S_2") (pintype "passive"))
    )
    (net (code "95") (name "/SD_VCC") (class "Default")
      (node (ref "C76") (pin "2") (pinfunction "2_2") (pintype "passive"))
      (node (ref "C80") (pin "2") (pinfunction "2_2") (pintype "passive"))
      (node (ref "JTAG") (pin "5") (pinfunction "5_5") (pintype "passive"))
      (node (ref "L6") (pin "2") (pinfunction "2_2") (pintype "passive"))
      (node (ref "SD") (pin "4") (pinfunction "VDD_4") (pintype "power_in"))
    )
    (net (code "96") (name "/SJTAG_PSW") (class "Default")
      (node (ref "PWR_BUT") (pin "1") (pinfunction "P_1") (pintype "passive"))
      (node (ref "R23") (pin "2") (pinfunction "2_2") (pintype "passive"))
      (node (ref "R24") (pin "2") (pinfunction "2_2") (pintype "passive"))
      (node (ref "REC") (pin "2") (pinfunction "2_2") (pintype "passive"))
      (node (ref "RM1") (pin "1.2") (pinfunction "2_1.2") (pintype "passive"))
      (node (ref "SJTAG") (pin "3") (pinfunction "3_3") (pintype "passive"))
    )
    (net (code "97") (name "/SSP1_CMD") (class "Default")
      (node (ref "JTAG") (pin "6") (pinfunction "6_6") (pintype "passive"))
      (node (ref "R21") (pin "1") (pinfunction "1_1") (pintype "passive"))
      (node (ref "SD") (pin "3") (pinfunction "CMD/DI_3") (pintype "input"))
      (node (ref "U1") (pin "83") (pinfunction "SSP1_CMD/SPI1_MOSI/JTAG_TDO_83") (pintype "bidirectional"))
    )
    (net (code "98") (name "/SSP1_DATA0") (class "Default")
      (node (ref "JTAG") (pin "2") (pinfunction "2_2") (pintype "passive"))
      (node (ref "RM1") (pin "3.1") (pinfunction "1_3.1") (pintype "passive"))
      (node (ref "SD") (pin "7") (pinfunction "DAT0/DO_7") (pintype "output"))
      (node (ref "U1") (pin "84") (pinfunction "SSP1_DATA0/SPI1_MISO/JTAG_TDI_84") (pintype "bidirectional"))
    )
    (net (code "99") (name "/SSP1_DATA1") (class "Default")
      (node (ref "JTAG") (pin "1") (pinfunction "1_1") (pintype "passive"))
      (node (ref "RM1") (pin "2.1") (pinfunction "1_2.1") (pintype "passive"))
      (node (ref "SD") (pin "8") (pinfunction "DAT1/RES_8") (pintype "bidirectional"))
      (node (ref "U1") (pin "85") (pinfunction "SSP1_DATA1/I2C_SCL/JTAG_TCLK_85") (pintype "bidirectional"))
    )
    (net (code "100") (name "/SSP1_DATA2") (class "Default")
      (node (ref "JTAG") (pin "8") (pinfunction "8_8") (pintype "passive"))
      (node (ref "RM1") (pin "4.1") (pinfunction "1_4.1") (pintype "passive"))
      (node (ref "SD") (pin "1") (pinfunction "DAT2/RES_1") (pintype "bidirectional"))
      (node (ref "U1") (pin "86") (pinfunction "SSP1_DATA2/I2C_SDA/JTAG_RTCK_86") (pintype "bidirectional"))
    )
    (net (code "101") (name "/SSP1_DATA3") (class "Default")
      (node (ref "JTAG") (pin "7") (pinfunction "7_7") (pintype "passive"))
      (node (ref "R20") (pin "1") (pinfunction "1_1") (pintype "passive"))
      (node (ref "SD") (pin "2") (pinfunction "CD/DAT3/CS_2") (pintype "input"))
      (node (ref "U1") (pin "87") (pinfunction "SSP1_DATA3/SPI1_SS#/JTAG_TMS_87") (pintype "bidirectional"))
    )
    (net (code "102") (name "/SSP1_SCK") (class "Default")
      (node (ref "JTAG") (pin "4") (pinfunction "4_4") (pintype "passive"))
      (node (ref "SD") (pin "5") (pinfunction "CLK/SCLK_5") (pintype "input"))
      (node (ref "U1") (pin "90") (pinfunction "SSP1_SCK/SPI1_SCK/JTAG_TRST_90") (pintype "bidirectional"))
    )
    (net (code "103") (name "/SSP2_MOSI") (class "Default")
      (node (ref "U1") (pin "21") (pinfunction "GPMI_RDY1/SSP2_CMD_21") (pintype "bidirectional"))
    )
    (net (code "104") (name "/SSP2_SCK") (class "Default")
      (node (ref "U1") (pin "33") (pinfunction "GPMI_WRN/SSP2_SCK_33") (pintype "bidirectional"))
    )
    (net (code "105") (name "/TEST_PAD") (class "Default")
      (node (ref "T_P") (pin "P$1") (pinfunction "PP_P$1") (pintype "passive"))
      (node (ref "U1") (pin "32") (pinfunction "GPMI_RDY0/SSP2_DETECT_32") (pintype "bidirectional"))
    )
    (net (code "106") (name "/USB_DM") (class "Default")
      (node (ref "U1") (pin "123") (pinfunction "USB_DM_123") (pintype "bidirectional"))
      (node (ref "U4") (pin "25") (pinfunction "DM0_25") (pintype "bidirectional"))
    )
    (net (code "107") (name "/USB_DP") (class "Default")
      (node (ref "U1") (pin "124") (pinfunction "USB_DP_124") (pintype "bidirectional"))
      (node (ref "U4") (pin "26") (pinfunction "DP0_26") (pintype "bidirectional"))
    )
    (net (code "108") (name "/VDDXTAL") (class "Default")
      (node (ref "C35") (pin "2") (pinfunction "2_2") (pintype "passive"))
      (node (ref "PWR_BUT") (pin "2") (pinfunction "S_2") (pintype "passive"))
      (node (ref "U1") (pin "120") (pinfunction "VDDXTAL_120") (pintype "passive"))
    )
    (net (code "109") (name "/WEN") (class "Default")
      (node (ref "U1") (pin "77") (pinfunction "EMI_WEN_77") (pintype "output"))
      (node (ref "U2") (pin "21") (pinfunction "#WE_21") (pintype "input"))
    )
    (net (code "110") (name "/X1") (class "Default")
      (node (ref "C42") (pin "2") (pinfunction "2_2") (pintype "passive"))
      (node (ref "Q2") (pin "2") (pinfunction "2_2") (pintype "passive"))
      (node (ref "U4") (pin "6") (pinfunction "X1_6") (pintype "input"))
    )
    (net (code "111") (name "/X2") (class "Default")
      (node (ref "C43") (pin "2") (pinfunction "2_2") (pintype "passive"))
      (node (ref "Q2") (pin "1") (pinfunction "1_1") (pintype "passive"))
      (node (ref "U4") (pin "7") (pinfunction "X2_7") (pintype "output"))
    )
    (net (code "112") (name "/XTALI") (class "Default")
      (node (ref "C32") (pin "2") (pinfunction "2_2") (pintype "passive"))
      (node (ref "Q1") (pin "2") (pinfunction "2_2") (pintype "passive"))
      (node (ref "T2") (pin "3") (pinfunction "C_3") (pintype "passive"))
      (node (ref "U1") (pin "122") (pinfunction "XTALI_122") (pintype "input"))
    )
    (net (code "113") (name "/XTALO") (class "Default")
      (node (ref "C33") (pin "2") (pinfunction "2_2") (pintype "passive"))
      (node (ref "Q1") (pin "1") (pinfunction "1_1") (pintype "passive"))
      (node (ref "T1") (pin "3") (pinfunction "C_3") (pintype "passive"))
      (node (ref "U1") (pin "121") (pinfunction "XTALO_121") (pintype "output"))
    )
    (net (code "114") (name "2.5V") (class "Default")
      (node (ref "C15") (pin "2") (pinfunction "2_2") (pintype "passive"))
      (node (ref "C16") (pin "2") (pinfunction "2_2") (pintype "passive"))
      (node (ref "C17") (pin "2") (pinfunction "2_2") (pintype "passive"))
      (node (ref "C22") (pin "2") (pinfunction "2_2") (pintype "passive"))
      (node (ref "C39") (pin "2") (pinfunction "2_2") (pintype "passive"))
      (node (ref "C57") (pin "2") (pinfunction "2_2") (pintype "passive"))
      (node (ref "C58") (pin "2") (pinfunction "2_2") (pintype "passive"))
      (node (ref "C60") (pin "2") (pinfunction "2_2") (pintype "passive"))
      (node (ref "C61") (pin "2") (pinfunction "2_2") (pintype "passive"))
      (node (ref "C62") (pin "2") (pinfunction "2_2") (pintype "passive"))
      (node (ref "C63") (pin "2") (pinfunction "2_2") (pintype "passive"))
      (node (ref "C64") (pin "2") (pinfunction "2_2") (pintype "passive"))
      (node (ref "C65") (pin "1") (pinfunction "1_1") (pintype "passive"))
      (node (ref "R1") (pin "2") (pinfunction "2_2") (pintype "passive"))
      (node (ref "R18") (pin "2") (pinfunction "2_2") (pintype "passive"))
      (node (ref "U1") (pin "106") (pinfunction "VDDM/LRADC4_106") (pintype "power_in"))
      (node (ref "U1") (pin "38") (pinfunction "VDDIO_EMIQ_38") (pintype "power_in"))
      (node (ref "U1") (pin "45") (pinfunction "VDDIO_EMI1_45") (pintype "power_in"))
      (node (ref "U1") (pin "53") (pinfunction "VDDIO_EMI2_53") (pintype "power_in"))
      (node (ref "U2") (pin "1") (pinfunction "VDD1_1") (pintype "power_in"))
      (node (ref "U2") (pin "15") (pinfunction "VDDQ3_15") (pintype "power_in"))
      (node (ref "U2") (pin "18") (pinfunction "VDD2_18") (pintype "power_in"))
      (node (ref "U2") (pin "3") (pinfunction "VDDQ1_3") (pintype "power_in"))
      (node (ref "U2") (pin "33") (pinfunction "VDD3_33") (pintype "power_in"))
      (node (ref "U2") (pin "55") (pinfunction "VDDQ4_55") (pintype "power_in"))
      (node (ref "U2") (pin "61") (pinfunction "VDDQ5_61") (pintype "power_in"))
      (node (ref "U2") (pin "9") (pinfunction "VDDQ2_9") (pintype "power_in"))
    )
    (net (code "115") (name "3.3VIO") (class "Default")
      (node (ref "C13") (pin "2") (pinfunction "2_2") (pintype "passive"))
      (node (ref "C14") (pin "2") (pinfunction "2_2") (pintype "passive"))
      (node (ref "C25") (pin "2") (pinfunction "2_2") (pintype "passive"))
      (node (ref "C26") (pin "2") (pinfunction "2_2") (pintype "passive"))
      (node (ref "D00_H") (pin "2") (pinfunction "2_2") (pintype "passive"))
      (node (ref "D01_H") (pin "2") (pinfunction "2_2") (pintype "passive"))
      (node (ref "D02_H") (pin "2") (pinfunction "2_2") (pintype "passive"))
      (node (ref "D03_H") (pin "2") (pinfunction "2_2") (pintype "passive"))
      (node (ref "L6") (pin "1") (pinfunction "1_1") (pintype "passive"))
      (node (ref "R15") (pin "1") (pinfunction "1_1") (pintype "passive"))
      (node (ref "R21") (pin "2") (pinfunction "2_2") (pintype "passive"))
      (node (ref "R25") (pin "2") (pinfunction "2_2") (pintype "passive"))
      (node (ref "R37") (pin "2") (pinfunction "2_2") (pintype "passive"))
      (node (ref "RESET") (pin "1") (pinfunction "P_1") (pintype "passive"))
      (node (ref "RM1") (pin "2.2") (pinfunction "2_2.2") (pintype "passive"))
      (node (ref "RM1") (pin "3.2") (pinfunction "2_3.2") (pintype "passive"))
      (node (ref "RM1") (pin "4.2") (pinfunction "2_4.2") (pintype "passive"))
      (node (ref "U1") (pin "18") (pinfunction "VDDIO33_1_18") (pintype "power_in"))
      (node (ref "U1") (pin "92") (pinfunction "VDDIO33_3_92") (pintype "power_in"))
      (node (ref "U1") (pin "95") (pinfunction "DCDC_VDDIO_95") (pintype "power_in"))
    )
    (net (code "116") (name "3.3VREG") (class "Default")
      (node (ref "GPIO_CON") (pin "38") (pinfunction "38_38") (pintype "passive"))
      (node (ref "SJTAG") (pin "1") (pinfunction "1_1") (pintype "passive"))
    )
    (net (code "117") (name "BAT") (class "Default")
      (node (ref "GPIO_CON") (pin "1") (pinfunction "1_1") (pintype "passive"))
    )
    (net (code "118") (name "GND") (class "Default")
      (node (ref "C1") (pin "-") (pinfunction "-_-") (pintype "passive"))
      (node (ref "C10") (pin "2") (pinfunction "2_2") (pintype "passive"))
      (node (ref "C11") (pin "1") (pinfunction "1_1") (pintype "passive"))
      (node (ref "C12") (pin "1") (pinfunction "1_1") (pintype "passive"))
      (node (ref "C13") (pin "1") (pinfunction "1_1") (pintype "passive"))
      (node (ref "C14") (pin "1") (pinfunction "1_1") (pintype "passive"))
      (node (ref "C15") (pin "1") (pinfunction "1_1") (pintype "passive"))
      (node (ref "C16") (pin "1") (pinfunction "1_1") (pintype "passive"))
      (node (ref "C17") (pin "1") (pinfunction "1_1") (pintype "passive"))
      (node (ref "C18") (pin "1") (pinfunction "1_1") (pintype "passive"))
      (node (ref "C19") (pin "1") (pinfunction "1_1") (pintype "passive"))
      (node (ref "C2") (pin "-") (pinfunction "-_-") (pintype "passive"))
      (node (ref "C20") (pin "1") (pinfunction "1_1") (pintype "passive"))
      (node (ref "C21") (pin "1") (pinfunction "1_1") (pintype "passive"))
      (node (ref "C22") (pin "1") (pinfunction "1_1") (pintype "passive"))
      (node (ref "C23") (pin "1") (pinfunction "1_1") (pintype "passive"))
      (node (ref "C24") (pin "1") (pinfunction "1_1") (pintype "passive"))
      (node (ref "C25") (pin "1") (pinfunction "1_1") (pintype "passive"))
      (node (ref "C26") (pin "1") (pinfunction "1_1") (pintype "passive"))
      (node (ref "C27") (pin "1") (pinfunction "1_1") (pintype "passive"))
      (node (ref "C28") (pin "1") (pinfunction "1_1") (pintype "passive"))
      (node (ref "C3") (pin "2") (pinfunction "2_2") (pintype "passive"))
      (node (ref "C32") (pin "1") (pinfunction "1_1") (pintype "passive"))
      (node (ref "C33") (pin "1") (pinfunction "1_1") (pintype "passive"))
      (node (ref "C34") (pin "1") (pinfunction "1_1") (pintype "passive"))
      (node (ref "C35") (pin "1") (pinfunction "1_1") (pintype "passive"))
      (node (ref "C36") (pin "1") (pinfunction "1_1") (pintype "passive"))
      (node (ref "C39") (pin "1") (pinfunction "1_1") (pintype "passive"))
      (node (ref "C4") (pin "2") (pinfunction "2_2") (pintype "passive"))
      (node (ref "C40") (pin "2") (pinfunction "2_2") (pintype "passive"))
      (node (ref "C41") (pin "2") (pinfunction "2_2") (pintype "passive"))
      (node (ref "C42") (pin "1") (pinfunction "1_1") (pintype "passive"))
      (node (ref "C43") (pin "1") (pinfunction "1_1") (pintype "passive"))
      (node (ref "C44") (pin "2") (pinfunction "2_2") (pintype "passive"))
      (node (ref "C45") (pin "2") (pinfunction "2_2") (pintype "passive"))
      (node (ref "C46") (pin "2") (pinfunction "2_2") (pintype "passive"))
      (node (ref "C47") (pin "2") (pinfunction "2_2") (pintype "passive"))
      (node (ref "C48") (pin "-") (pinfunction "-_-") (pintype "passive"))
      (node (ref "C49") (pin "2") (pinfunction "2_2") (pintype "passive"))
      (node (ref "C5") (pin "2") (pinfunction "2_2") (pintype "passive"))
      (node (ref "C50") (pin "2") (pinfunction "2_2") (pintype "passive"))
      (node (ref "C51") (pin "2") (pinfunction "2_2") (pintype "passive"))
      (node (ref "C52") (pin "2") (pinfunction "2_2") (pintype "passive"))
      (node (ref "C53") (pin "-") (pinfunction "-_-") (pintype "passive"))
      (node (ref "C54") (pin "2") (pinfunction "2_2") (pintype "passive"))
      (node (ref "C55") (pin "-") (pinfunction "-_-") (pintype "passive"))
      (node (ref "C56") (pin "2") (pinfunction "2_2") (pintype "passive"))
      (node (ref "C57") (pin "1") (pinfunction "1_1") (pintype "passive"))
      (node (ref "C58") (pin "1") (pinfunction "1_1") (pintype "passive"))
      (node (ref "C59") (pin "1") (pinfunction "1_1") (pintype "passive"))
      (node (ref "C6") (pin "2") (pinfunction "2_2") (pintype "passive"))
      (node (ref "C60") (pin "1") (pinfunction "1_1") (pintype "passive"))
      (node (ref "C61") (pin "1") (pinfunction "1_1") (pintype "passive"))
      (node (ref "C62") (pin "1") (pinfunction "1_1") (pintype "passive"))
      (node (ref "C63") (pin "1") (pinfunction "1_1") (pintype "passive"))
      (node (ref "C64") (pin "1") (pinfunction "1_1") (pintype "passive"))
      (node (ref "C66") (pin "1") (pinfunction "1_1") (pintype "passive"))
      (node (ref "C7") (pin "2") (pinfunction "2_2") (pintype "passive"))
      (node (ref "C76") (pin "1") (pinfunction "1_1") (pintype "passive"))
      (node (ref "C8") (pin "-") (pinfunction "-_-") (pintype "passive"))
      (node (ref "C80") (pin "1") (pinfunction "1_1") (pintype "passive"))
      (node (ref "C82") (pin "1") (pinfunction "1_1") (pintype "passive"))
      (node (ref "C83") (pin "1") (pinfunction "1_1") (pintype "passive"))
      (node (ref "C9") (pin "-") (pinfunction "-_-") (pintype "passive"))
      (node (ref "GPIO_CON") (pin "2") (pinfunction "2_2") (pintype "passive"))
      (node (ref "GPIO_CON") (pin "40") (pinfunction "40_40") (pintype "passive"))
      (node (ref "IC1") (pin "3") (pinfunction "GND_3") (pintype "passive"))
      (node (ref "IC2") (pin "3") (pinfunction "GND_3") (pintype "passive"))
      (node (ref "JTAG") (pin "3") (pinfunction "3_3") (pintype "passive"))
      (node (ref "L1") (pin "1") (pinfunction "1_1") (pintype "passive"))
      (node (ref "PWR_JACK") (pin "1") (pinfunction "1_1") (pintype "passive"))
      (node (ref "PWR_JACK") (pin "2") (pinfunction "2_2") (pintype "passive"))
      (node (ref "R10") (pin "2") (pinfunction "2_2") (pintype "passive"))
      (node (ref "R14") (pin "1") (pinfunction "1_1") (pintype "passive"))
      (node (ref "R16") (pin "1") (pinfunction "1_1") (pintype "passive"))
      (node (ref "R19") (pin "1") (pinfunction "1_1") (pintype "passive"))
      (node (ref "R2") (pin "1") (pinfunction "1_1") (pintype "passive"))
      (node (ref "R20") (pin "2") (pinfunction "2_2") (pintype "passive"))
      (node (ref "R27") (pin "1") (pinfunction "1_1") (pintype "passive"))
      (node (ref "R28") (pin "1") (pinfunction "1_1") (pintype "passive"))
      (node (ref "R29") (pin "1") (pinfunction "1_1") (pintype "passive"))
      (node (ref "R3") (pin "1") (pinfunction "1_1") (pintype "passive"))
      (node (ref "R31") (pin "1") (pinfunction "1_1") (pintype "passive"))
      (node (ref "R32") (pin "1") (pinfunction "1_1") (pintype "passive"))
      (node (ref "R33") (pin "1") (pinfunction "1_1") (pintype "passive"))
      (node (ref "R34") (pin "1") (pinfunction "1_1") (pintype "passive"))
      (node (ref "R36") (pin "1") (pinfunction "1_1") (pintype "passive"))
      (node (ref "R39") (pin "2") (pinfunction "2_2") (pintype "passive"))
      (node (ref "R4") (pin "1") (pinfunction "1_1") (pintype "passive"))
      (node (ref "RM1") (pin "1.1") (pinfunction "1_1.1") (pintype "passive"))
      (node (ref "RM2") (pin "1.1") (pinfunction "1.1_1.1") (pintype "passive"))
      (node (ref "RM2") (pin "2.1") (pinfunction "2.1_2.1") (pintype "passive"))
      (node (ref "RM2") (pin "3.1") (pinfunction "3.1_3.1") (pintype "passive"))
      (node (ref "RM2") (pin "4.1") (pinfunction "4.1_4.1") (pintype "passive"))
      (node (ref "SD") (pin "6") (pinfunction "VSS_6") (pintype "power_in"))
      (node (ref "SJTAG") (pin "2") (pinfunction "2_2") (pintype "passive"))
      (node (ref "T1") (pin "1") (pinfunction "B_1") (pintype "passive"))
      (node (ref "T1") (pin "2") (pinfunction "E_2") (pintype "passive"))
      (node (ref "T2") (pin "2") (pinfunction "E_2") (pintype "passive"))
      (node (ref "U1") (pin "105") (pinfunction "VSSA4_105") (pintype "power_in"))
      (node (ref "U1") (pin "112") (pinfunction "VSSA1_112") (pintype "power_in"))
      (node (ref "U1") (pin "118") (pinfunction "VSSA2_118") (pintype "power_in"))
      (node (ref "U1") (pin "30") (pinfunction "VSSD1_30") (pintype "power_in"))
      (node (ref "U1") (pin "35") (pinfunction "VSSD2_35") (pintype "power_in"))
      (node (ref "U1") (pin "98") (pinfunction "DCDC_GND_98") (pintype "power_in"))
      (node (ref "U2") (pin "12") (pinfunction "VSSQ2_12") (pintype "power_in"))
      (node (ref "U2") (pin "34") (pinfunction "VSS1_34") (pintype "power_in"))
      (node (ref "U2") (pin "48") (pinfunction "VSS2_48") (pintype "power_in"))
      (node (ref "U2") (pin "52") (pinfunction "VSSQ3_52") (pintype "power_in"))
      (node (ref "U2") (pin "58") (pinfunction "VSSQ4_58") (pintype "power_in"))
      (node (ref "U2") (pin "6") (pinfunction "VSSQ1_6") (pintype "power_in"))
      (node (ref "U2") (pin "64") (pinfunction "VSSQ5_64") (pintype "power_in"))
      (node (ref "U2") (pin "66") (pinfunction "VSS3_66") (pintype "power_in"))
      (node (ref "U3") (pin "2") (pinfunction "GND_2") (pintype "power_in"))
      (node (ref "U4") (pin "14") (pinfunction "TEST_14") (pintype "input"))
      (node (ref "U4") (pin "15") (pinfunction "GND_15") (pintype "power_in"))
      (node (ref "U_DEBUG") (pin "3") (pinfunction "3_3") (pintype "passive"))
      (node (ref "X1") (pin "4") (pinfunction "4_4") (pintype "passive"))
      (node (ref "X2") (pin "4") (pinfunction "4_4") (pintype "passive"))
    )
    (net (code "119") (name "Net-(C10-Pad1)") (class "Default")
      (node (ref "C10") (pin "1") (pinfunction "1_1") (pintype "passive"))
      (node (ref "L2") (pin "2") (pinfunction "2_2") (pintype "passive"))
    )
    (net (code "120") (name "Net-(C40-Pad1)") (class "Default")
      (node (ref "C40") (pin "1") (pinfunction "1_1") (pintype "passive"))
      (node (ref "R24") (pin "1") (pinfunction "1_1") (pintype "passive"))
    )
    (net (code "121") (name "Net-(C44-Pad1)") (class "Default")
      (node (ref "C44") (pin "1") (pinfunction "1_1") (pintype "passive"))
      (node (ref "C45") (pin "1") (pinfunction "1_1") (pintype "passive"))
      (node (ref "C46") (pin "1") (pinfunction "1_1") (pintype "passive"))
      (node (ref "L7") (pin "2") (pinfunction "2_2") (pintype "passive"))
      (node (ref "U4") (pin "1") (pinfunction "AVDD_1") (pintype "power_in"))
      (node (ref "U4") (pin "10") (pinfunction "AVDD_10") (pintype "power_in"))
      (node (ref "U4") (pin "5") (pinfunction "AVDD_5") (pintype "power_in"))
    )
    (net (code "122") (name "Net-(C52-Pad1)") (class "Default")
      (node (ref "C52") (pin "1") (pinfunction "1_1") (pintype "passive"))
      (node (ref "L8") (pin "2") (pinfunction "2_2") (pintype "passive"))
      (node (ref "X1") (pin "1") (pinfunction "1_1") (pintype "passive"))
    )
    (net (code "123") (name "Net-(C54-Pad1)") (class "Default")
      (node (ref "C54") (pin "1") (pinfunction "1_1") (pintype "passive"))
      (node (ref "L4") (pin "2") (pinfunction "2_2") (pintype "passive"))
      (node (ref "X2") (pin "1") (pinfunction "1_1") (pintype "passive"))
    )
    (net (code "124") (name "Net-(C56-Pad1)") (class "Default")
      (node (ref "C56") (pin "1") (pinfunction "1_1") (pintype "passive"))
      (node (ref "L9") (pin "2") (pinfunction "2_2") (pintype "passive"))
    )
    (net (code "125") (name "Net-(D00_H-Pad1)") (class "Default")
      (node (ref "D00_H") (pin "1") (pinfunction "1_1") (pintype "passive"))
      (node (ref "RM3") (pin "4.2") (pinfunction "4.2_4.2") (pintype "passive"))
    )
    (net (code "126") (name "Net-(D01_H-Pad1)") (class "Default")
      (node (ref "D01_H") (pin "1") (pinfunction "1_1") (pintype "passive"))
      (node (ref "RM3") (pin "3.2") (pinfunction "3.2_3.2") (pintype "passive"))
    )
    (net (code "127") (name "Net-(D02_H-Pad1)") (class "Default")
      (node (ref "D02_H") (pin "1") (pinfunction "1_1") (pintype "passive"))
      (node (ref "RM3") (pin "2.2") (pinfunction "2.2_2.2") (pintype "passive"))
    )
    (net (code "128") (name "Net-(D03_H-Pad1)") (class "Default")
      (node (ref "D03_H") (pin "1") (pinfunction "1_1") (pintype "passive"))
      (node (ref "RM3") (pin "1.2") (pinfunction "1.2_1.2") (pintype "passive"))
    )
    (net (code "129") (name "Net-(IC1-VI)") (class "Default")
      (node (ref "C1") (pin "+") (pinfunction "+_+") (pintype "passive"))
      (node (ref "C2") (pin "+") (pinfunction "+_+") (pintype "passive"))
      (node (ref "C4") (pin "1") (pinfunction "1_1") (pintype "passive"))
      (node (ref "C5") (pin "1") (pinfunction "1_1") (pintype "passive"))
      (node (ref "C6") (pin "1") (pinfunction "1_1") (pintype "passive"))
      (node (ref "IC1") (pin "1") (pinfunction "VI_1") (pintype "input"))
      (node (ref "PWR_JACK") (pin "3") (pinfunction "3_3") (pintype "passive"))
    )
    (net (code "130") (name "Net-(L1-Pad2)") (class "Default")
      (node (ref "L1") (pin "2") (pinfunction "2_2") (pintype "passive"))
      (node (ref "X1") (pin "S1") (pinfunction "S1_S1") (pintype "passive"))
      (node (ref "X1") (pin "S2") (pinfunction "S2_S2") (pintype "passive"))
      (node (ref "X2") (pin "S1") (pinfunction "S1_S1") (pintype "passive"))
      (node (ref "X2") (pin "S2") (pinfunction "S2_S2") (pintype "passive"))
    )
    (net (code "131") (name "Net-(LED1-PadC)") (class "Default")
      (node (ref "LED1") (pin "C") (pinfunction "C_C") (pintype "passive"))
      (node (ref "R4") (pin "2") (pinfunction "2_2") (pintype "passive"))
    )
    (net (code "132") (name "Net-(R25-Pad1)") (class "Default")
      (node (ref "R25") (pin "1") (pinfunction "1_1") (pintype "passive"))
      (node (ref "REC") (pin "1") (pinfunction "1_1") (pintype "passive"))
    )
    (net (code "133") (name "Net-(T2-B)") (class "Default")
      (node (ref "R10") (pin "1") (pinfunction "1_1") (pintype "passive"))
      (node (ref "R42") (pin "1") (pinfunction "1_1") (pintype "passive"))
      (node (ref "T2") (pin "1") (pinfunction "B_1") (pintype "passive"))
    )
    (net (code "134") (name "Net-(U1-DCDC_LN1)") (class "Default")
      (node (ref "C82") (pin "2") (pinfunction "2_2") (pintype "passive"))
      (node (ref "L10") (pin "2") (pinfunction "2_2") (pintype "passive"))
      (node (ref "U1") (pin "97") (pinfunction "DCDC_LN1_97") (pintype "passive"))
    )
    (net (code "135") (name "Net-(U1-DCDC_LP)") (class "Default")
      (node (ref "C83") (pin "2") (pinfunction "2_2") (pintype "passive"))
      (node (ref "L10") (pin "1") (pinfunction "1_1") (pintype "passive"))
      (node (ref "U1") (pin "99") (pinfunction "DCDC_LP_99") (pintype "passive"))
    )
    (net (code "136") (name "Net-(U1-VAG)") (class "Default")
      (node (ref "C34") (pin "2") (pinfunction "2_2") (pintype "passive"))
      (node (ref "U1") (pin "117") (pinfunction "VAG_117") (pintype "passive"))
    )
    (net (code "137") (name "Net-(U1-VDD4P2)") (class "Default")
      (node (ref "C18") (pin "2") (pinfunction "2_2") (pintype "passive"))
      (node (ref "C19") (pin "2") (pinfunction "2_2") (pintype "passive"))
      (node (ref "U1") (pin "101") (pinfunction "VDD4P2_101") (pintype "power_in"))
    )
    (net (code "138") (name "Net-(U2-VREF)") (class "Default")
      (node (ref "C65") (pin "2") (pinfunction "2_2") (pintype "passive"))
      (node (ref "C66") (pin "2") (pinfunction "2_2") (pintype "passive"))
      (node (ref "R18") (pin "1") (pinfunction "1_1") (pintype "passive"))
      (node (ref "R19") (pin "2") (pinfunction "2_2") (pintype "passive"))
      (node (ref "U2") (pin "49") (pinfunction "VREF_49") (pintype "input"))
    )
    (net (code "139") (name "Net-(U3-ISET)") (class "Default")
      (node (ref "R27") (pin "2") (pinfunction "2_2") (pintype "passive"))
      (node (ref "U3") (pin "3") (pinfunction "ISET_3") (pintype "bidirectional"))
    )
    (net (code "140") (name "Net-(U3-OUT)") (class "Default")
      (node (ref "C48") (pin "+") (pinfunction "+_+") (pintype "passive"))
      (node (ref "C53") (pin "+") (pinfunction "+_+") (pintype "passive"))
      (node (ref "C55") (pin "+") (pinfunction "+_+") (pintype "passive"))
      (node (ref "C9") (pin "+") (pinfunction "+_+") (pintype "passive"))
      (node (ref "L2") (pin "1") (pinfunction "1_1") (pintype "passive"))
      (node (ref "L4") (pin "1") (pinfunction "1_1") (pintype "passive"))
      (node (ref "L8") (pin "1") (pinfunction "1_1") (pintype "passive"))
      (node (ref "L9") (pin "1") (pinfunction "1_1") (pintype "passive"))
      (node (ref "U3") (pin "1") (pinfunction "OUT_1") (pintype "bidirectional"))
    )
    (net (code "141") (name "Net-(U4-#RESET)") (class "Default")
      (node (ref "C59") (pin "2") (pinfunction "2_2") (pintype "passive"))
      (node (ref "R39") (pin "1") (pinfunction "1_1") (pintype "passive"))
      (node (ref "R40") (pin "1") (pinfunction "1_1") (pintype "passive"))
      (node (ref "U4") (pin "13") (pinfunction "#RESET_13") (pintype "bidirectional"))
    )
    (net (code "142") (name "Net-(U4-DM1)") (class "Default")
      (node (ref "R31") (pin "2") (pinfunction "2_2") (pintype "passive"))
      (node (ref "U4") (pin "27") (pinfunction "DM1_27") (pintype "bidirectional"))
      (node (ref "X1") (pin "2") (pinfunction "2_2") (pintype "passive"))
    )
    (net (code "143") (name "Net-(U4-DM2)") (class "Default")
      (node (ref "R33") (pin "2") (pinfunction "2_2") (pintype "passive"))
      (node (ref "U4") (pin "2") (pinfunction "DM2_2") (pintype "bidirectional"))
      (node (ref "X2") (pin "2") (pinfunction "2_2") (pintype "passive"))
    )
    (net (code "144") (name "Net-(U4-DP1)") (class "Default")
      (node (ref "R32") (pin "2") (pinfunction "2_2") (pintype "passive"))
      (node (ref "U4") (pin "28") (pinfunction "DP1_28") (pintype "bidirectional"))
      (node (ref "X1") (pin "3") (pinfunction "3_3") (pintype "passive"))
    )
    (net (code "145") (name "Net-(U4-DP2)") (class "Default")
      (node (ref "R34") (pin "2") (pinfunction "2_2") (pintype "passive"))
      (node (ref "U4") (pin "3") (pinfunction "DP2_3") (pintype "bidirectional"))
      (node (ref "X2") (pin "3") (pinfunction "3_3") (pintype "passive"))
    )
    (net (code "146") (name "Net-(U4-DVDD)") (class "Default")
      (node (ref "C47") (pin "1") (pinfunction "1_1") (pintype "passive"))
      (node (ref "C49") (pin "1") (pinfunction "1_1") (pintype "passive"))
      (node (ref "L7") (pin "1") (pinfunction "1_1") (pintype "passive"))
      (node (ref "R30") (pin "1") (pinfunction "1_1") (pintype "passive"))
      (node (ref "U4") (pin "16") (pinfunction "DVDD_16") (pintype "power_in"))
      (node (ref "U4") (pin "24") (pinfunction "V33_24") (pintype "power_in"))
    )
    (net (code "147") (name "Net-(U4-PGANG)") (class "Default")
      (node (ref "R30") (pin "2") (pinfunction "2_2") (pintype "passive"))
      (node (ref "U4") (pin "18") (pinfunction "PGANG_18") (pintype "bidirectional"))
    )
    (net (code "148") (name "Net-(U4-RREF)") (class "Default")
      (node (ref "R29") (pin "2") (pinfunction "2_2") (pintype "passive"))
      (node (ref "U4") (pin "4") (pinfunction "RREF_4") (pintype "bidirectional"))
    )
    (net (code "149") (name "VIN") (class "Default")
      (node (ref "GPIO_CON") (pin "39") (pinfunction "39_39") (pintype "passive"))
    )
    (net (code "150") (name "unconnected-(U1-BATT-Pad103)") (class "Default")
      (node (ref "U1") (pin "103") (pinfunction "BATT_103") (pintype "input"))
    )
    (net (code "151") (name "unconnected-(U1-HPL-Pad113)") (class "Default")
      (node (ref "U1") (pin "113") (pinfunction "HPL_113") (pintype "output"))
    )
    (net (code "152") (name "unconnected-(U1-HPR-Pad109)") (class "Default")
      (node (ref "U1") (pin "109") (pinfunction "HPR_109") (pintype "output"))
    )
    (net (code "153") (name "unconnected-(U1-LINE1_INL-Pad115)") (class "Default")
      (node (ref "U1") (pin "115") (pinfunction "LINE1_INL_115") (pintype "input"))
    )
    (net (code "154") (name "unconnected-(U1-LINE1_INR-Pad114)") (class "Default")
      (node (ref "U1") (pin "114") (pinfunction "LINE1_INR_114") (pintype "input"))
    )
    (net (code "155") (name "unconnected-(U1-VDAC1-Pad104)") (class "Default")
      (node (ref "U1") (pin "104") (pinfunction "VDAC1_104") (pintype "output"))
    )
    (net (code "156") (name "unconnected-(U2-NC1-Pad14)") (class "Default")
      (node (ref "U2") (pin "14") (pinfunction "NC1_14") (pintype "no_connect"))
    )
    (net (code "157") (name "unconnected-(U2-NC2-Pad17)") (class "Default")
      (node (ref "U2") (pin "17") (pinfunction "NC2_17") (pintype "no_connect"))
    )
    (net (code "158") (name "unconnected-(U2-NC3-Pad19)") (class "Default")
      (node (ref "U2") (pin "19") (pinfunction "NC3_19") (pintype "no_connect"))
    )
    (net (code "159") (name "unconnected-(U2-NC4-Pad25)") (class "Default")
      (node (ref "U2") (pin "25") (pinfunction "NC4_25") (pintype "no_connect"))
    )
    (net (code "160") (name "unconnected-(U2-NC5-Pad43)") (class "Default")
      (node (ref "U2") (pin "43") (pinfunction "NC5_43") (pintype "no_connect"))
    )
    (net (code "161") (name "unconnected-(U2-NC6-Pad50)") (class "Default")
      (node (ref "U2") (pin "50") (pinfunction "NC6_50") (pintype "no_connect"))
    )
    (net (code "162") (name "unconnected-(U2-NC7-Pad53)") (class "Default")
      (node (ref "U2") (pin "53") (pinfunction "NC7_53") (pintype "no_connect"))
    )
    (net (code "163") (name "unconnected-(U4-#OVCUR1-Pad21)") (class "Default")
      (node (ref "U4") (pin "21") (pinfunction "#OVCUR1_21") (pintype "bidirectional"))
    )
    (net (code "164") (name "unconnected-(U4-#OVCUR2-Pad19)") (class "Default")
      (node (ref "U4") (pin "19") (pinfunction "#OVCUR2_19") (pintype "bidirectional"))
    )
    (net (code "165") (name "unconnected-(U4-#PWREN1-Pad22)") (class "Default")
      (node (ref "U4") (pin "22") (pinfunction "#PWREN1_22") (pintype "output"))
    )
    (net (code "166") (name "unconnected-(U4-#PWREN2-Pad20)") (class "Default")
      (node (ref "U4") (pin "20") (pinfunction "#PWREN2_20") (pintype "output"))
    )
    (net (code "167") (name "unconnected-(U4-PSELF-Pad17)") (class "Default")
      (node (ref "U4") (pin "17") (pinfunction "PSELF_17") (pintype "bidirectional"))
    )
  )
)
